# TRACKER_SOM_EVAL_BOARD_v1_0.net
KiCad netlist of a schematic drawn in EAGLE
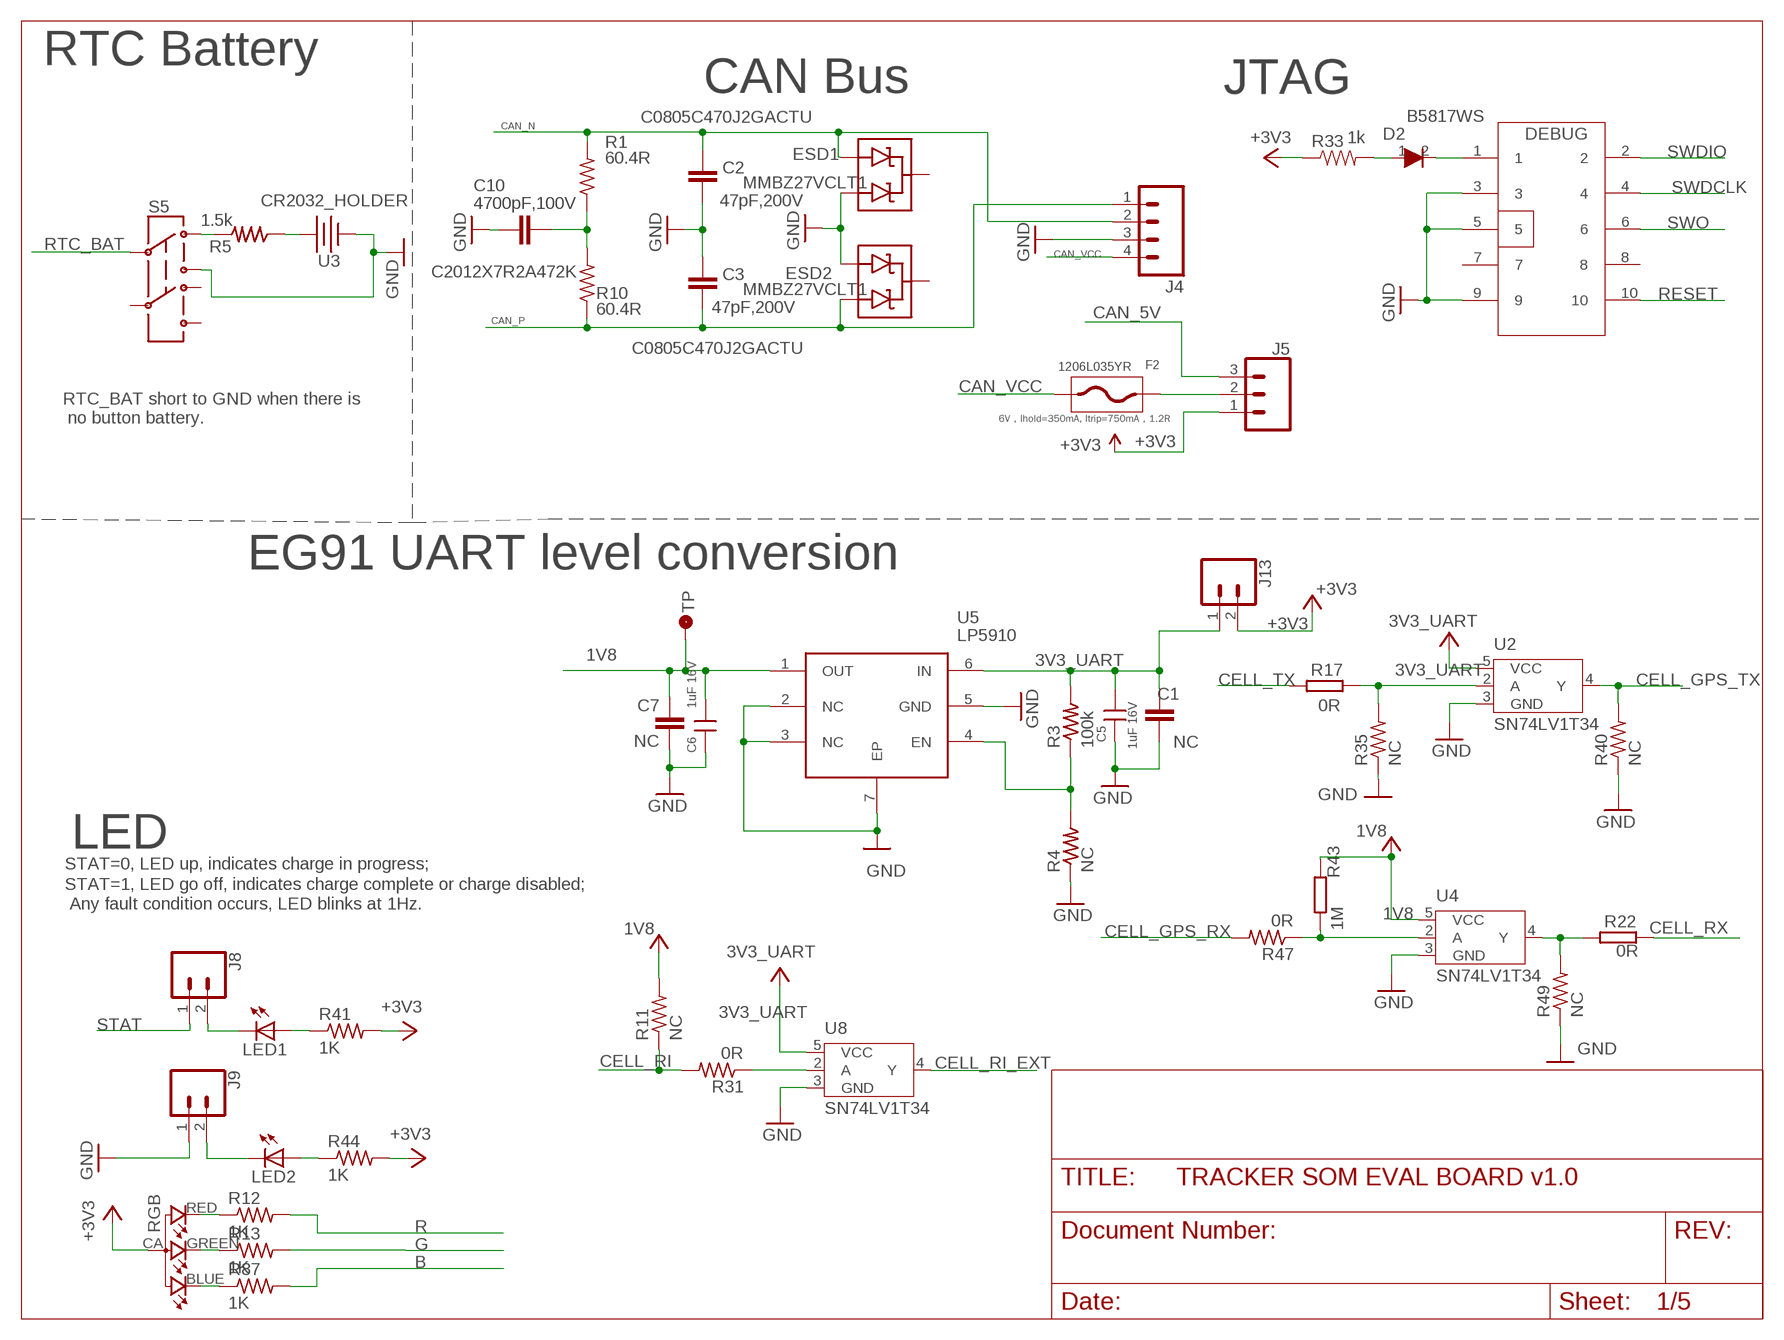
[diagram p0: schematic, sheet 1]
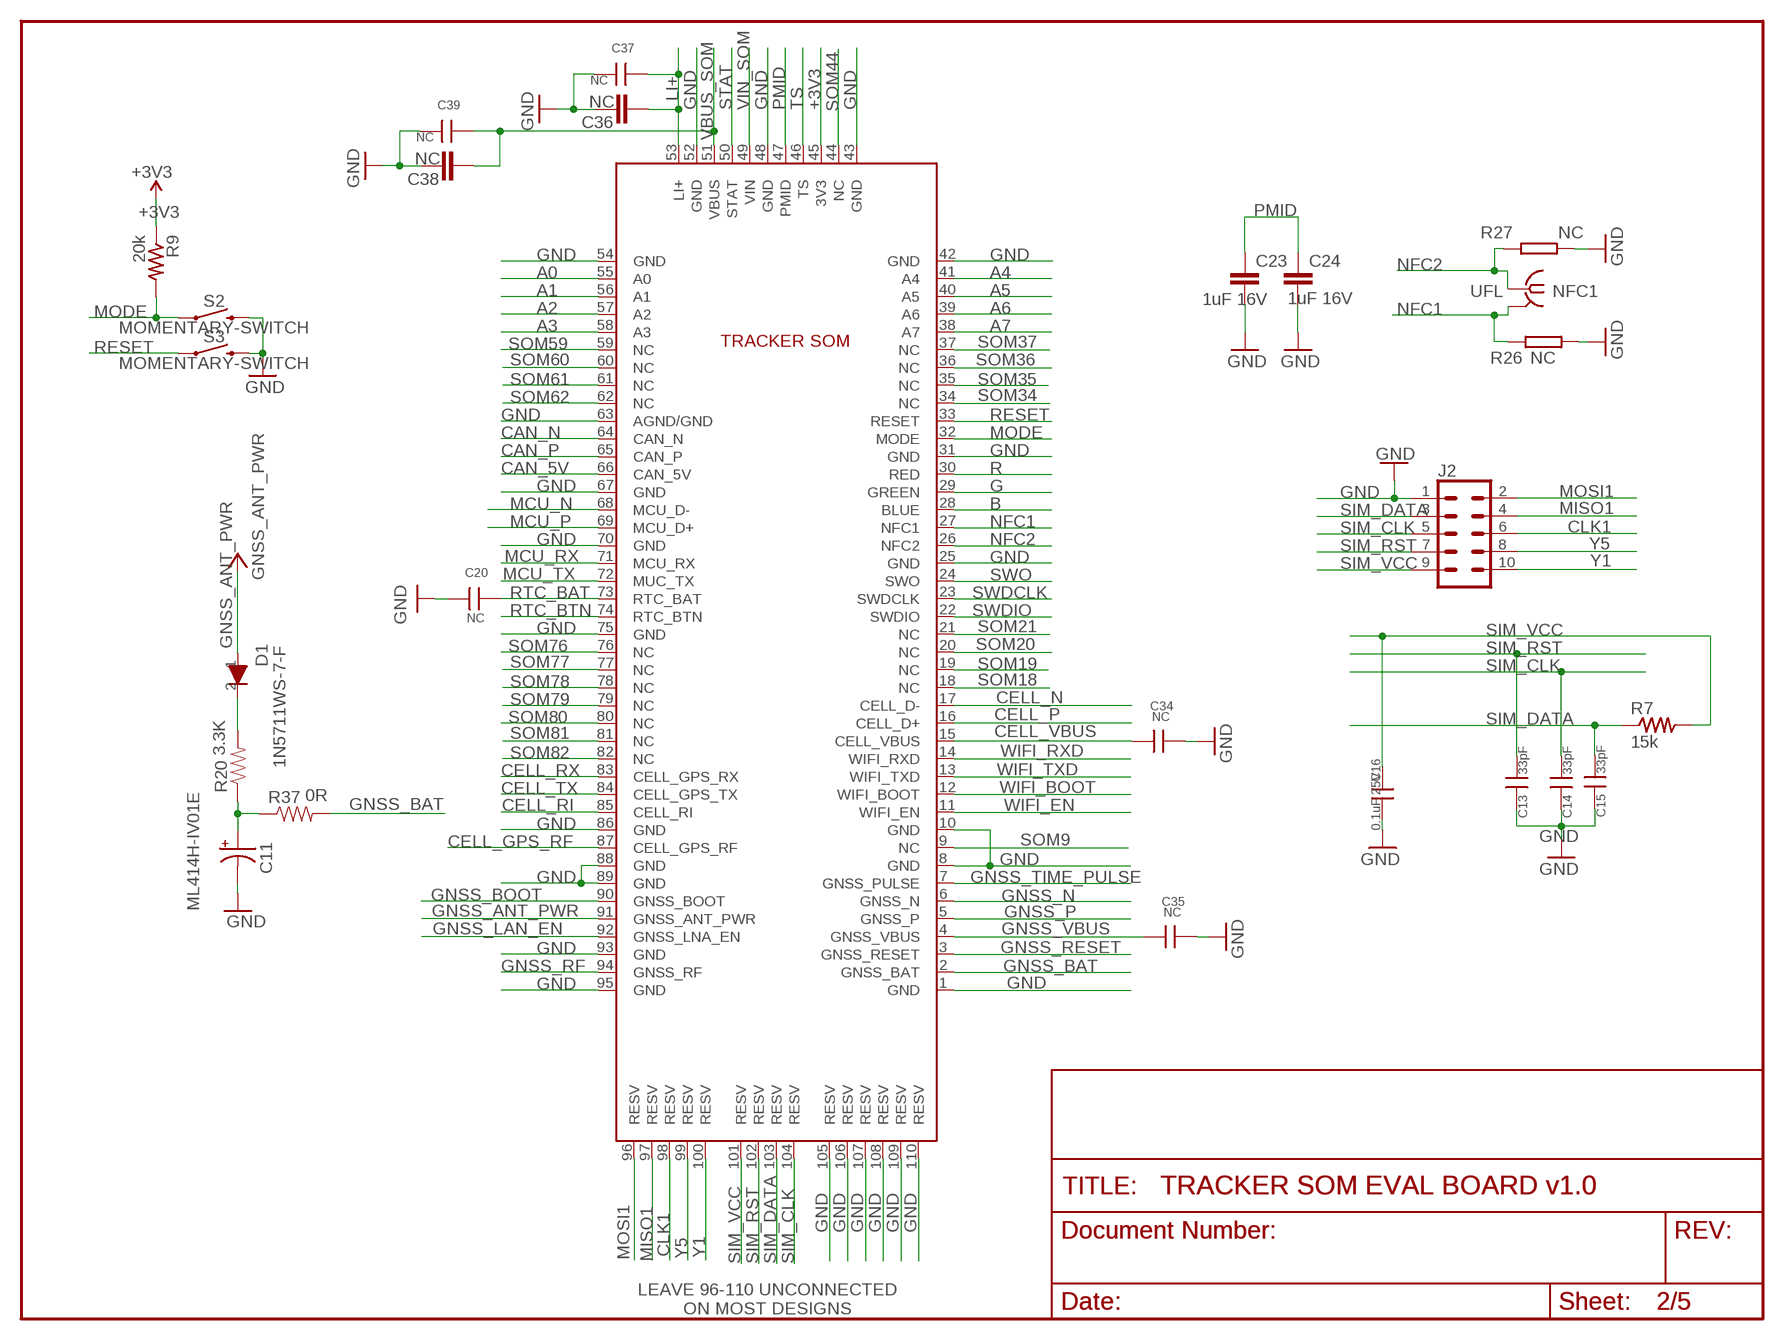
[diagram p1: schematic, sheet 2]
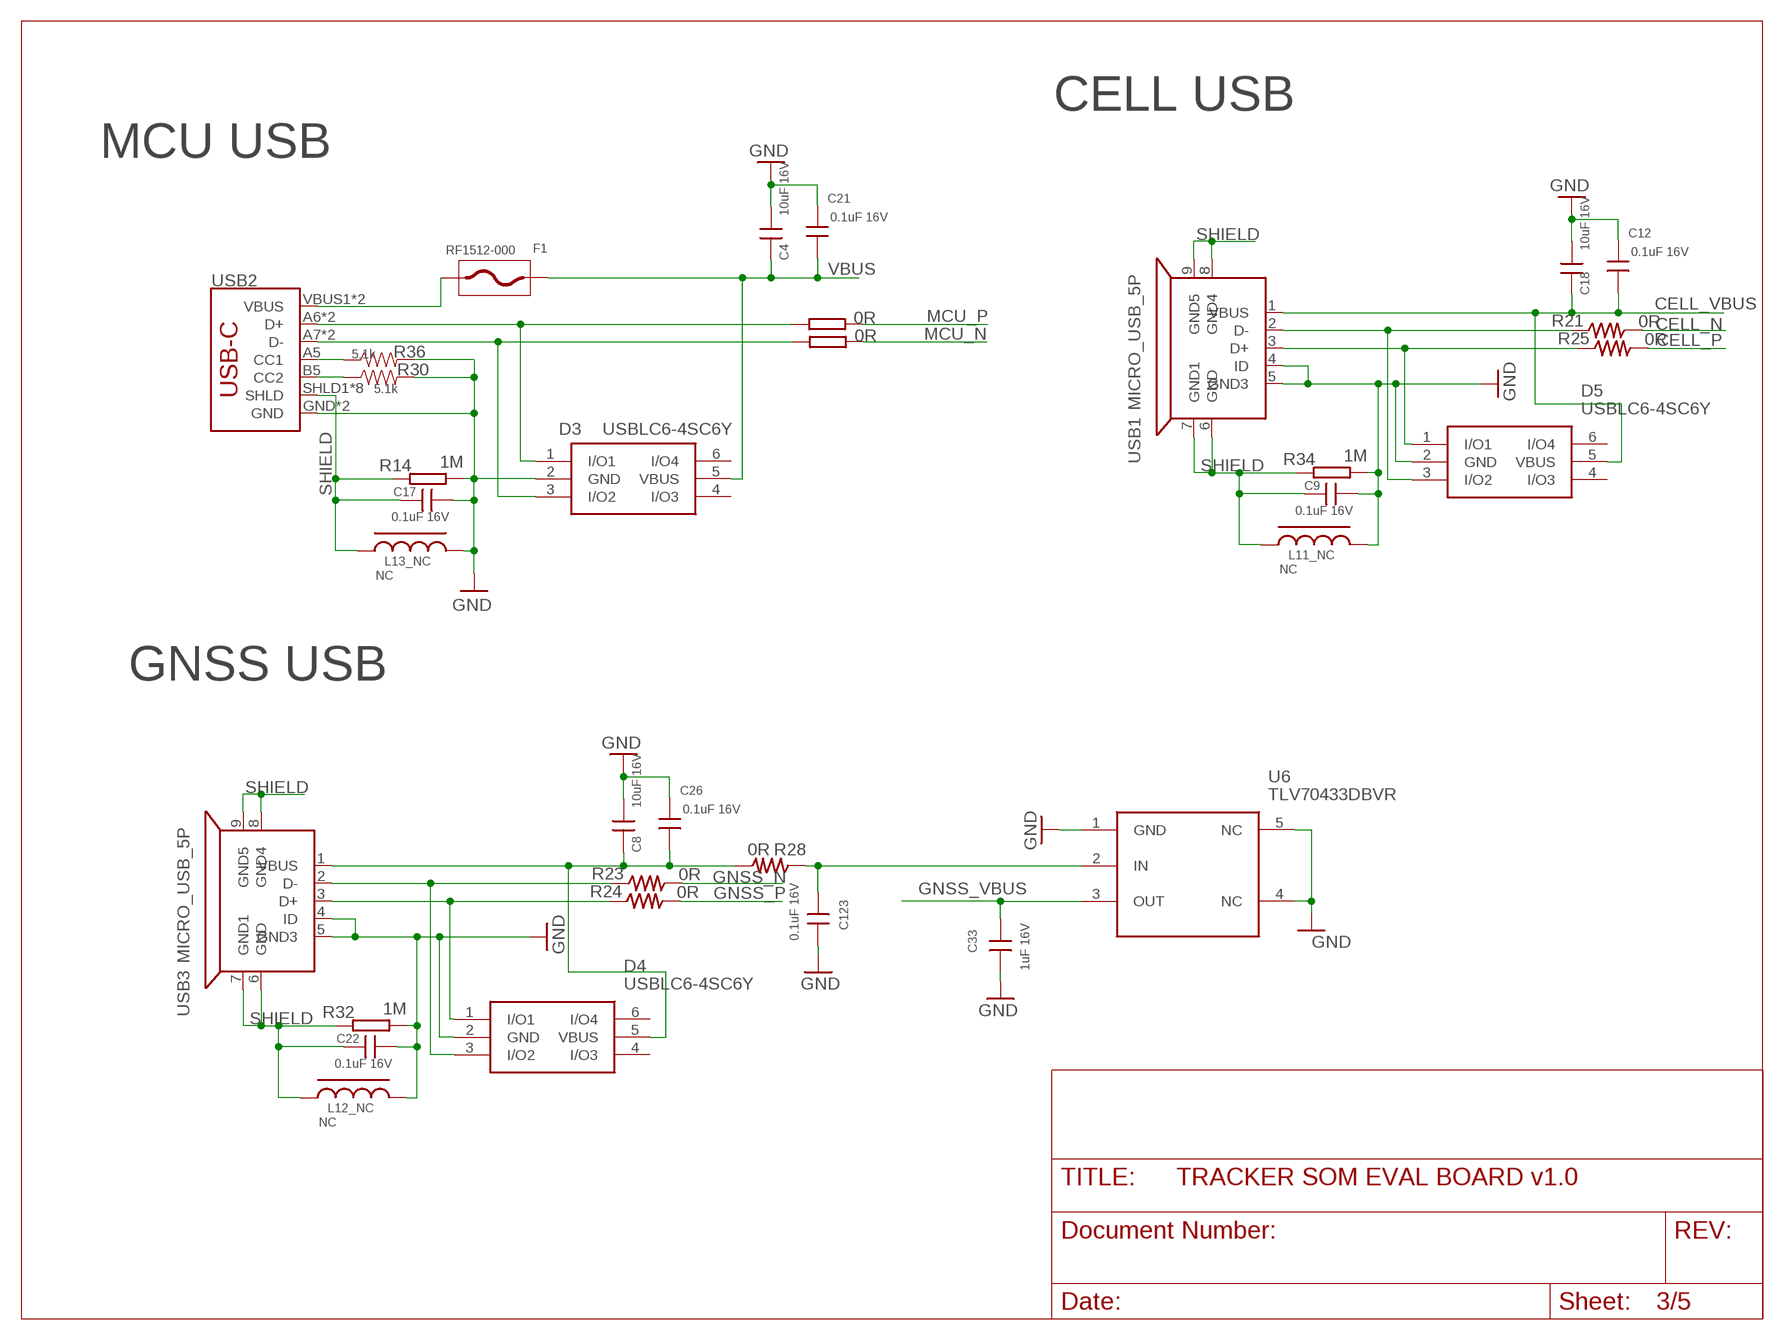
[diagram p2: schematic, sheet 3]
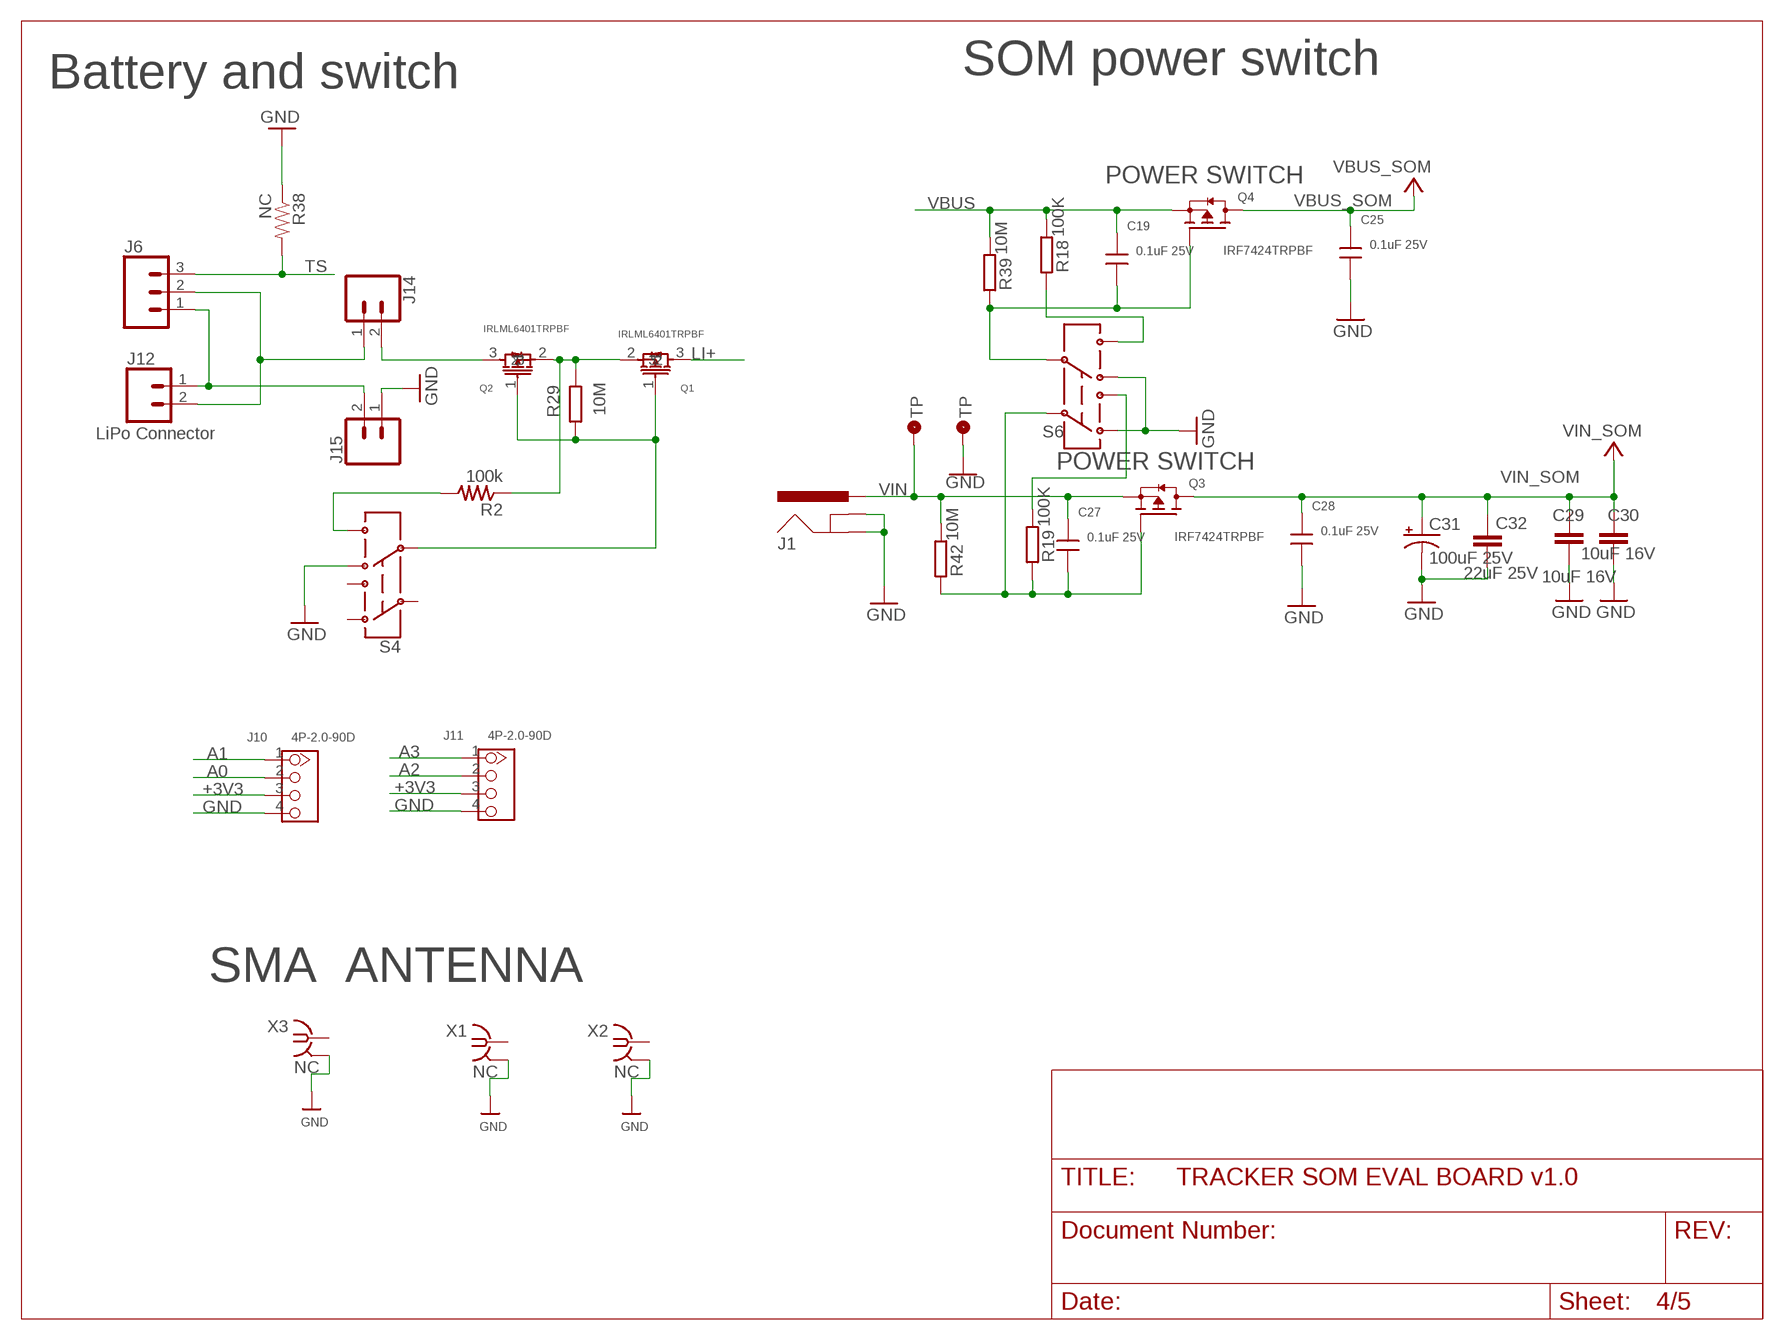
[diagram p3: schematic, sheet 4]
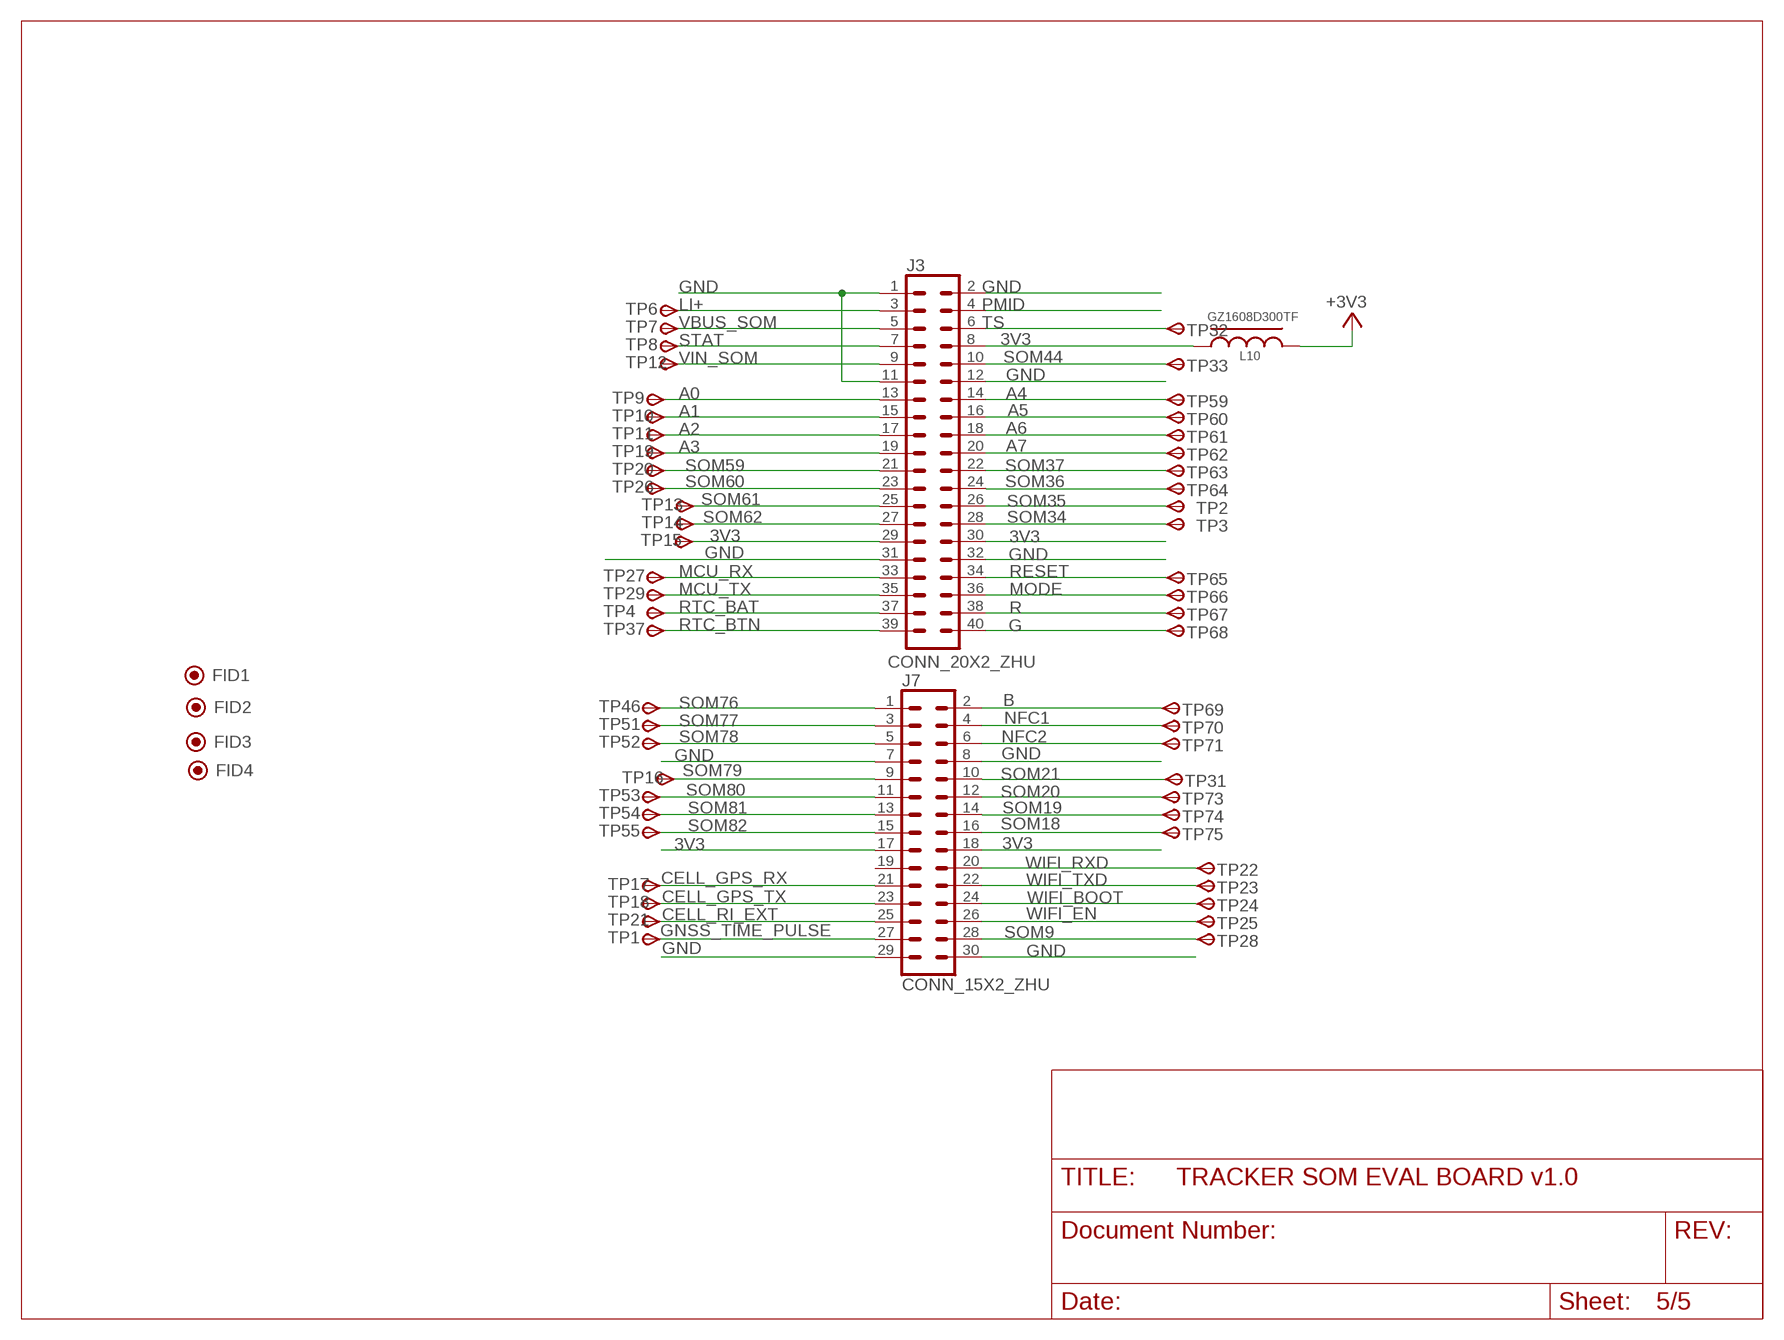
[diagram p4: schematic, sheet 5]

(export (version "E")
  (design (tool "Eeschema 10.0.6"))
  (components
    (comp (ref "FID1")
      (value "FIDUCIAL_2")
      (footprint "eagle-import:FID_TOP_1MM")
      (libsource (lib "eagle-import") (part "FIDUCIAL_2"))
    )
    (comp (ref "FID2")
      (value "FIDUCIAL_2")
      (footprint "eagle-import:FID_TOP_1MM")
      (libsource (lib "eagle-import") (part "FIDUCIAL_2"))
    )
    (comp (ref "FID3")
      (value "FIDUCIAL_2")
      (footprint "eagle-import:FID_TOP_1MM")
      (libsource (lib "eagle-import") (part "FIDUCIAL_2"))
    )
    (comp (ref "FID4")
      (value "FIDUCIAL_2")
      (footprint "eagle-import:FID_TOP_1MM")
      (libsource (lib "eagle-import") (part "FIDUCIAL_2"))
    )
    (comp (ref "J3")
      (value "CONN_20X2_ZHU")
      (footprint "eagle-import:SMD_2_20")
      (libsource (lib "eagle-import") (part "CONN_20X2_ZHU"))
    )
    (comp (ref "J7")
      (value "CONN_15X2_ZHU")
      (footprint "eagle-import:SMD_2_15")
      (libsource (lib "eagle-import") (part "CONN_15X2_ZHU"))
    )
    (comp (ref "L10")
      (value "GZ1608D300TF")
      (footprint "eagle-import:R-0603A")
      (libsource (lib "eagle-import") (part "L"))
    )
    (comp (ref "TP1")
      (value "TPSB1,27")
      (footprint "eagle-import:B1,27")
      (libsource (lib "eagle-import") (part "TPSB1,27"))
    )
    (comp (ref "TP2")
      (value "TPSB1,27")
      (footprint "eagle-import:B1,27")
      (libsource (lib "eagle-import") (part "TPSB1,27"))
    )
    (comp (ref "TP3")
      (value "TPSB1,27")
      (footprint "eagle-import:B1,27")
      (libsource (lib "eagle-import") (part "TPSB1,27"))
    )
    (comp (ref "TP4")
      (value "TPSB1,27")
      (footprint "eagle-import:B1,27")
      (libsource (lib "eagle-import") (part "TPSB1,27"))
    )
    (comp (ref "TP6")
      (value "TPSB1,27")
      (footprint "eagle-import:B1,27")
      (libsource (lib "eagle-import") (part "TPSB1,27"))
    )
    (comp (ref "TP7")
      (value "TPSB1,27")
      (footprint "eagle-import:B1,27")
      (libsource (lib "eagle-import") (part "TPSB1,27"))
    )
    (comp (ref "TP8")
      (value "TPSB1,27")
      (footprint "eagle-import:B1,27")
      (libsource (lib "eagle-import") (part "TPSB1,27"))
    )
    (comp (ref "TP9")
      (value "TPSB1,27")
      (footprint "eagle-import:B1,27")
      (libsource (lib "eagle-import") (part "TPSB1,27"))
    )
    (comp (ref "TP10")
      (value "TPSB1,27")
      (footprint "eagle-import:B1,27")
      (libsource (lib "eagle-import") (part "TPSB1,27"))
    )
    (comp (ref "TP11")
      (value "TPSB1,27")
      (footprint "eagle-import:B1,27")
      (libsource (lib "eagle-import") (part "TPSB1,27"))
    )
    (comp (ref "TP12")
      (value "TPSB1,27")
      (footprint "eagle-import:B1,27")
      (libsource (lib "eagle-import") (part "TPSB1,27"))
    )
    (comp (ref "TP13")
      (value "TPSB1,27")
      (footprint "eagle-import:B1,27")
      (libsource (lib "eagle-import") (part "TPSB1,27"))
    )
    (comp (ref "TP14")
      (value "TPSB1,27")
      (footprint "eagle-import:B1,27")
      (libsource (lib "eagle-import") (part "TPSB1,27"))
    )
    (comp (ref "TP15")
      (value "TPSB1,27")
      (footprint "eagle-import:B1,27")
      (libsource (lib "eagle-import") (part "TPSB1,27"))
    )
    (comp (ref "TP16")
      (value "TPSB1,27")
      (footprint "eagle-import:B1,27")
      (libsource (lib "eagle-import") (part "TPSB1,27"))
    )
    (comp (ref "TP17")
      (value "TPSB1,27")
      (footprint "eagle-import:B1,27")
      (libsource (lib "eagle-import") (part "TPSB1,27"))
    )
    (comp (ref "TP18")
      (value "TPSB1,27")
      (footprint "eagle-import:B1,27")
      (libsource (lib "eagle-import") (part "TPSB1,27"))
    )
    (comp (ref "TP19")
      (value "TPSB1,27")
      (footprint "eagle-import:B1,27")
      (libsource (lib "eagle-import") (part "TPSB1,27"))
    )
    (comp (ref "TP20")
      (value "TPSB1,27")
      (footprint "eagle-import:B1,27")
      (libsource (lib "eagle-import") (part "TPSB1,27"))
    )
    (comp (ref "TP21")
      (value "TPSB1,27")
      (footprint "eagle-import:B1,27")
      (libsource (lib "eagle-import") (part "TPSB1,27"))
    )
    (comp (ref "TP22")
      (value "TPSB1,27")
      (footprint "eagle-import:B1,27")
      (libsource (lib "eagle-import") (part "TPSB1,27"))
    )
    (comp (ref "TP23")
      (value "TPSB1,27")
      (footprint "eagle-import:B1,27")
      (libsource (lib "eagle-import") (part "TPSB1,27"))
    )
    (comp (ref "TP24")
      (value "TPSB1,27")
      (footprint "eagle-import:B1,27")
      (libsource (lib "eagle-import") (part "TPSB1,27"))
    )
    (comp (ref "TP25")
      (value "TPSB1,27")
      (footprint "eagle-import:B1,27")
      (libsource (lib "eagle-import") (part "TPSB1,27"))
    )
    (comp (ref "TP26")
      (value "TPSB1,27")
      (footprint "eagle-import:B1,27")
      (libsource (lib "eagle-import") (part "TPSB1,27"))
    )
    (comp (ref "TP27")
      (value "TPSB1,27")
      (footprint "eagle-import:B1,27")
      (libsource (lib "eagle-import") (part "TPSB1,27"))
    )
    (comp (ref "TP28")
      (value "TPSB1,27")
      (footprint "eagle-import:B1,27")
      (libsource (lib "eagle-import") (part "TPSB1,27"))
    )
    (comp (ref "TP29")
      (value "TPSB1,27")
      (footprint "eagle-import:B1,27")
      (libsource (lib "eagle-import") (part "TPSB1,27"))
    )
    (comp (ref "TP31")
      (value "TPSB1,27")
      (footprint "eagle-import:B1,27")
      (libsource (lib "eagle-import") (part "TPSB1,27"))
    )
    (comp (ref "TP32")
      (value "TPSB1,27")
      (footprint "eagle-import:B1,27")
      (libsource (lib "eagle-import") (part "TPSB1,27"))
    )
    (comp (ref "TP33")
      (value "TPSB1,27")
      (footprint "eagle-import:B1,27")
      (libsource (lib "eagle-import") (part "TPSB1,27"))
    )
    (comp (ref "TP37")
      (value "TPSB1,27")
      (footprint "eagle-import:B1,27")
      (libsource (lib "eagle-import") (part "TPSB1,27"))
    )
    (comp (ref "TP46")
      (value "TPSB1,27")
      (footprint "eagle-import:B1,27")
      (libsource (lib "eagle-import") (part "TPSB1,27"))
    )
    (comp (ref "TP51")
      (value "TPSB1,27")
      (footprint "eagle-import:B1,27")
      (libsource (lib "eagle-import") (part "TPSB1,27"))
    )
    (comp (ref "TP52")
      (value "TPSB1,27")
      (footprint "eagle-import:B1,27")
      (libsource (lib "eagle-import") (part "TPSB1,27"))
    )
    (comp (ref "TP53")
      (value "TPSB1,27")
      (footprint "eagle-import:B1,27")
      (libsource (lib "eagle-import") (part "TPSB1,27"))
    )
    (comp (ref "TP54")
      (value "TPSB1,27")
      (footprint "eagle-import:B1,27")
      (libsource (lib "eagle-import") (part "TPSB1,27"))
    )
    (comp (ref "TP55")
      (value "TPSB1,27")
      (footprint "eagle-import:B1,27")
      (libsource (lib "eagle-import") (part "TPSB1,27"))
    )
    (comp (ref "TP59")
      (value "TPSB1,27")
      (footprint "eagle-import:B1,27")
      (libsource (lib "eagle-import") (part "TPSB1,27"))
    )
    (comp (ref "TP60")
      (value "TPSB1,27")
      (footprint "eagle-import:B1,27")
      (libsource (lib "eagle-import") (part "TPSB1,27"))
    )
    (comp (ref "TP61")
      (value "TPSB1,27")
      (footprint "eagle-import:B1,27")
      (libsource (lib "eagle-import") (part "TPSB1,27"))
    )
    (comp (ref "TP62")
      (value "TPSB1,27")
      (footprint "eagle-import:B1,27")
      (libsource (lib "eagle-import") (part "TPSB1,27"))
    )
    (comp (ref "TP63")
      (value "TPSB1,27")
      (footprint "eagle-import:B1,27")
      (libsource (lib "eagle-import") (part "TPSB1,27"))
    )
    (comp (ref "TP64")
      (value "TPSB1,27")
      (footprint "eagle-import:B1,27")
      (libsource (lib "eagle-import") (part "TPSB1,27"))
    )
    (comp (ref "TP65")
      (value "TPSB1,27")
      (footprint "eagle-import:B1,27")
      (libsource (lib "eagle-import") (part "TPSB1,27"))
    )
    (comp (ref "TP66")
      (value "TPSB1,27")
      (footprint "eagle-import:B1,27")
      (libsource (lib "eagle-import") (part "TPSB1,27"))
    )
    (comp (ref "TP67")
      (value "TPSB1,27")
      (footprint "eagle-import:B1,27")
      (libsource (lib "eagle-import") (part "TPSB1,27"))
    )
    (comp (ref "TP68")
      (value "TPSB1,27")
      (footprint "eagle-import:B1,27")
      (libsource (lib "eagle-import") (part "TPSB1,27"))
    )
    (comp (ref "TP69")
      (value "TPSB1,27")
      (footprint "eagle-import:B1,27")
      (libsource (lib "eagle-import") (part "TPSB1,27"))
    )
    (comp (ref "TP70")
      (value "TPSB1,27")
      (footprint "eagle-import:B1,27")
      (libsource (lib "eagle-import") (part "TPSB1,27"))
    )
    (comp (ref "TP71")
      (value "TPSB1,27")
      (footprint "eagle-import:B1,27")
      (libsource (lib "eagle-import") (part "TPSB1,27"))
    )
    (comp (ref "TP73")
      (value "TPSB1,27")
      (footprint "eagle-import:B1,27")
      (libsource (lib "eagle-import") (part "TPSB1,27"))
    )
    (comp (ref "TP74")
      (value "TPSB1,27")
      (footprint "eagle-import:B1,27")
      (libsource (lib "eagle-import") (part "TPSB1,27"))
    )
    (comp (ref "TP75")
      (value "TPSB1,27")
      (footprint "eagle-import:B1,27")
      (libsource (lib "eagle-import") (part "TPSB1,27"))
    )
    (comp (ref "C4")
      (value "10uF 16V")
      (footprint "eagle-import:REDBEAR_C0603")
      (libsource (lib "eagle-import") (part "REDBEAR_CAPC0603"))
    )
    (comp (ref "C8")
      (value "10uF 16V")
      (footprint "eagle-import:REDBEAR_C0603")
      (libsource (lib "eagle-import") (part "REDBEAR_CAPC0603"))
    )
    (comp (ref "C9")
      (value "0.1uF 16V")
      (footprint "eagle-import:PARTICLE-SZ_C-0402")
      (libsource (lib "eagle-import") (part "PARTICLE-SZ_CAP0402"))
    )
    (comp (ref "C12")
      (value "0.1uF 16V")
      (footprint "eagle-import:C-0402")
      (libsource (lib "eagle-import") (part "RedBear_CAP0402"))
    )
    (comp (ref "C17")
      (value "0.1uF 16V")
      (footprint "eagle-import:PARTICLE-SZ_C-0402")
      (libsource (lib "eagle-import") (part "PARTICLE-SZ_CAP0402"))
    )
    (comp (ref "C18")
      (value "10uF 16V")
      (footprint "eagle-import:REDBEAR_C0603")
      (libsource (lib "eagle-import") (part "REDBEAR_CAPC0603"))
    )
    (comp (ref "C21")
      (value "0.1uF 16V")
      (footprint "eagle-import:C-0402")
      (libsource (lib "eagle-import") (part "RedBear_CAP0402"))
    )
    (comp (ref "C22")
      (value "0.1uF 16V")
      (footprint "eagle-import:PARTICLE-SZ_C-0402")
      (libsource (lib "eagle-import") (part "PARTICLE-SZ_CAP0402"))
    )
    (comp (ref "C26")
      (value "0.1uF 16V")
      (footprint "eagle-import:C-0402")
      (libsource (lib "eagle-import") (part "RedBear_CAP0402"))
    )
    (comp (ref "C33")
      (value "1uF 16V")
      (footprint "eagle-import:C0603")
      (libsource (lib "eagle-import") (part "CAPC0603"))
    )
    (comp (ref "C123")
      (value "0.1uF 16V")
      (footprint "eagle-import:C-0402")
      (libsource (lib "eagle-import") (part "particle SZ_CAP0402"))
    )
    (comp (ref "D3")
      (value "USBLC6-4SC6Y")
      (footprint "eagle-import:SOT95P280X145-6N")
      (fields (field (name "MOUSER_PART_NUMBER") "511-USBLC6-4SC6Y"))
      (libsource (lib "eagle-import") (part "USBLC6-4SC6Y"))
    )
    (comp (ref "D4")
      (value "USBLC6-4SC6Y")
      (footprint "eagle-import:SOT95P280X145-6N")
      (fields (field (name "MOUSER_PART_NUMBER") "511-USBLC6-4SC6Y"))
      (libsource (lib "eagle-import") (part "USBLC6-4SC6Y"))
    )
    (comp (ref "D5")
      (value "USBLC6-4SC6Y")
      (footprint "eagle-import:SOT95P280X145-6N")
      (fields (field (name "MOUSER_PART_NUMBER") "511-USBLC6-4SC6Y"))
      (libsource (lib "eagle-import") (part "USBLC6-4SC6Y"))
    )
    (comp (ref "F1")
      (value "RF1512-000")
      (footprint "eagle-import:R1206")
      (libsource (lib "eagle-import") (part "FUSEF1206"))
    )
    (comp (ref "L11_NC")
      (value "NC")
      (footprint "eagle-import:R-0603A")
      (libsource (lib "eagle-import") (part "L"))
    )
    (comp (ref "L12_NC")
      (value "NC")
      (footprint "eagle-import:R-0603A")
      (libsource (lib "eagle-import") (part "L"))
    )
    (comp (ref "L13_NC")
      (value "NC")
      (footprint "eagle-import:R-0603A")
      (libsource (lib "eagle-import") (part "L"))
    )
    (comp (ref "R14")
      (value "1M")
      (footprint "eagle-import:REDBEAR_R0603")
      (libsource (lib "eagle-import") (part "REDBEAR_RESR0603"))
    )
    (comp (ref "R15")
      (value "0R")
      (footprint "eagle-import:R-0402S")
      (libsource (lib "eagle-import") (part "RES0402S"))
    )
    (comp (ref "R16")
      (value "0R")
      (footprint "eagle-import:R-0402S")
      (libsource (lib "eagle-import") (part "RES0402S"))
    )
    (comp (ref "R21")
      (value "0R")
      (footprint "eagle-import:R-0402S")
      (libsource (lib "eagle-import") (part "particle SZ_RES0402S"))
    )
    (comp (ref "R23")
      (value "0R")
      (footprint "eagle-import:R-0402S")
      (libsource (lib "eagle-import") (part "particle SZ_RES0402S"))
    )
    (comp (ref "R24")
      (value "0R")
      (footprint "eagle-import:R-0402S")
      (libsource (lib "eagle-import") (part "particle SZ_RES0402S"))
    )
    (comp (ref "R25")
      (value "0R")
      (footprint "eagle-import:R-0402S")
      (libsource (lib "eagle-import") (part "particle SZ_RES0402S"))
    )
    (comp (ref "R28")
      (value "0R")
      (footprint "eagle-import:R-0402S")
      (libsource (lib "eagle-import") (part "particle SZ_RES0402S"))
    )
    (comp (ref "R30")
      (value "5.1k")
      (footprint "eagle-import:C0402")
      (libsource (lib "eagle-import") (part "SparkFun_RESISTOR0402"))
    )
    (comp (ref "R32")
      (value "1M")
      (footprint "eagle-import:REDBEAR_R0603")
      (libsource (lib "eagle-import") (part "REDBEAR_RESR0603"))
    )
    (comp (ref "R34")
      (value "1M")
      (footprint "eagle-import:REDBEAR_R0603")
      (libsource (lib "eagle-import") (part "REDBEAR_RESR0603"))
    )
    (comp (ref "R36")
      (value "5.1k")
      (footprint "eagle-import:C0402")
      (libsource (lib "eagle-import") (part "SparkFun_RESISTOR0402"))
    )
    (comp (ref "U6")
      (value "TLV70433DBVR")
      (footprint "eagle-import:TLV70433DBVR")
      (libsource (lib "eagle-import") (part "TLV70433DBVR"))
    )
    (comp (ref "USB1")
      (value "MICRO_USB_5P")
      (footprint "eagle-import:MICRO_USB")
      (libsource (lib "eagle-import") (part "MICRO_USBMICRO_USB"))
    )
    (comp (ref "USB2")
      (value "USB_C16PIN")
      (footprint "eagle-import:USB-C-16P")
      (libsource (lib "eagle-import") (part "USB_C16PIN"))
    )
    (comp (ref "USB3")
      (value "MICRO_USB_5P")
      (footprint "eagle-import:MICRO_USB")
      (libsource (lib "eagle-import") (part "MICRO_USBMICRO_USB"))
    )
    (comp (ref "C1")
      (value "NC")
      (footprint "eagle-import:C0805")
      (libsource (lib "eagle-import") (part "C-EUC0805"))
    )
    (comp (ref "C2")
      (value "47pF,200V")
      (footprint "eagle-import:C0805")
      (fields (field (name "PART_NUMBER") "C0805C470J2GACTU"))
      (libsource (lib "eagle-import") (part "C-EUC0805"))
    )
    (comp (ref "C3")
      (value "47pF,200V")
      (footprint "eagle-import:C0805")
      (fields (field (name "PART_NUMBER") "C0805C470J2GACTU"))
      (libsource (lib "eagle-import") (part "C-EUC0805"))
    )
    (comp (ref "C5")
      (value "1uF 16V")
      (footprint "eagle-import:C0603")
      (libsource (lib "eagle-import") (part "CAPC0603"))
    )
    (comp (ref "C6")
      (value "1uF 16V")
      (footprint "eagle-import:C0603")
      (libsource (lib "eagle-import") (part "CAPC0603"))
    )
    (comp (ref "C7")
      (value "NC")
      (footprint "eagle-import:C0805")
      (libsource (lib "eagle-import") (part "C-EUC0805"))
    )
    (comp (ref "C10")
      (value "4700pF,100V")
      (footprint "eagle-import:C0805")
      (fields (field (name "PART_NUMBER") "C2012X7R2A472K"))
      (libsource (lib "eagle-import") (part "C-EUC0805"))
    )
    (comp (ref "D2")
      (value "B5817WS")
      (footprint "eagle-import:SOD-323")
      (libsource (lib "eagle-import") (part "DIODESOD323"))
    )
    (comp (ref "DEBUG")
      (value "CON 2X5P")
      (footprint "eagle-import:CON5X2_1.27")
      (libsource (lib "eagle-import") (part "CON5X2"))
    )
    (comp (ref "ESD1")
      (value "MMBZ27VCLT1")
      (footprint "eagle-import:SOT23-3")
      (libsource (lib "eagle-import") (part "MMBZ27VCLT1"))
    )
    (comp (ref "ESD2")
      (value "MMBZ27VCLT1")
      (footprint "eagle-import:SOT23-3")
      (libsource (lib "eagle-import") (part "MMBZ27VCLT1"))
    )
    (comp (ref "F2")
      (value "1206L035YR")
      (footprint "eagle-import:R1206")
      (libsource (lib "eagle-import") (part "FUSEF1206"))
    )
    (comp (ref "J4")
      (value "M04SCREW")
      (footprint "eagle-import:SCREWTERMINAL-3.5MM-4")
      (fields (field (name "PARTNO") "OSTTE040104"))
      (libsource (lib "eagle-import") (part "M04SCREW"))
    )
    (comp (ref "J5")
      (value "CONN_03_2.54MM")
      (footprint "eagle-import:1X03")
      (libsource (lib "eagle-import") (part "CONN_03_2.54MM"))
    )
    (comp (ref "J8")
      (value "CONN_02")
      (footprint "eagle-import:1X02")
      (libsource (lib "eagle-import") (part "CONN_02"))
    )
    (comp (ref "J9")
      (value "CONN_02")
      (footprint "eagle-import:1X02")
      (libsource (lib "eagle-import") (part "CONN_02"))
    )
    (comp (ref "J13")
      (value "CONN_02")
      (footprint "eagle-import:1X02")
      (libsource (lib "eagle-import") (part "CONN_02"))
    )
    (comp (ref "LED1")
      (value "LED0603")
      (footprint "eagle-import:LED-0603")
      (libsource (lib "eagle-import") (part "LED0603"))
    )
    (comp (ref "LED2")
      (value "LED0603")
      (footprint "eagle-import:LED-0603")
      (libsource (lib "eagle-import") (part "LED0603"))
    )
    (comp (ref "R1")
      (value "60.4R")
      (footprint "eagle-import:R1206")
      (libsource (lib "eagle-import") (part "rcl_334_R-US_R1206"))
    )
    (comp (ref "R3")
      (value "100k")
      (footprint "eagle-import:R-0402S")
      (libsource (lib "eagle-import") (part "particle SZ_RES0402S"))
    )
    (comp (ref "R4")
      (value "NC")
      (footprint "eagle-import:R-0402S")
      (libsource (lib "eagle-import") (part "particle SZ_RES0402S"))
    )
    (comp (ref "R5")
      (value "1.5k")
      (footprint "eagle-import:R-0402S")
      (libsource (lib "eagle-import") (part "particle SZ_RES0402S"))
    )
    (comp (ref "R10")
      (value "60.4R")
      (footprint "eagle-import:R1206")
      (libsource (lib "eagle-import") (part "rcl_334_R-US_R1206"))
    )
    (comp (ref "R11")
      (value "NC")
      (footprint "eagle-import:R0402_B")
      (libsource (lib "eagle-import") (part "R-US_"))
    )
    (comp (ref "R12")
      (value "1K")
      (footprint "eagle-import:R0603")
      (libsource (lib "eagle-import") (part "R-US_R0603"))
    )
    (comp (ref "R13")
      (value "1K")
      (footprint "eagle-import:R0603")
      (libsource (lib "eagle-import") (part "R-US_R0603"))
    )
    (comp (ref "R17")
      (value "0R")
      (footprint "eagle-import:R0603")
      (libsource (lib "eagle-import") (part "RESR0603"))
    )
    (comp (ref "R22")
      (value "0R")
      (footprint "eagle-import:R0603")
      (libsource (lib "eagle-import") (part "RESR0603"))
    )
    (comp (ref "R31")
      (value "0R")
      (footprint "eagle-import:R0402_B")
      (libsource (lib "eagle-import") (part "R-US_"))
    )
    (comp (ref "R33")
      (value "1k")
      (footprint "eagle-import:0603")
      (libsource (lib "eagle-import") (part "RESISTOR0603"))
    )
    (comp (ref "R35")
      (value "NC")
      (footprint "eagle-import:R0402_B")
      (libsource (lib "eagle-import") (part "R-US_"))
    )
    (comp (ref "R40")
      (value "NC")
      (footprint "eagle-import:R0402_B")
      (libsource (lib "eagle-import") (part "R-US_"))
    )
    (comp (ref "R41")
      (value "1K")
      (footprint "eagle-import:R0603")
      (libsource (lib "eagle-import") (part "R-US_R0603"))
    )
    (comp (ref "R43")
      (value "1M")
      (footprint "eagle-import:REDBEAR_R0603")
      (libsource (lib "eagle-import") (part "REDBEAR_RESR0603"))
    )
    (comp (ref "R44")
      (value "1K")
      (footprint "eagle-import:R0603")
      (libsource (lib "eagle-import") (part "R-US_R0603"))
    )
    (comp (ref "R47")
      (value "0R")
      (footprint "eagle-import:R0402_B")
      (libsource (lib "eagle-import") (part "R-US_"))
    )
    (comp (ref "R49")
      (value "NC")
      (footprint "eagle-import:R0402_B")
      (libsource (lib "eagle-import") (part "R-US_"))
    )
    (comp (ref "R87")
      (value "1K")
      (footprint "eagle-import:R0603")
      (libsource (lib "eagle-import") (part "R-US_R0603"))
    )
    (comp (ref "RGB")
      (value "RGB-LED-CLMVB-FKARGB")
      (footprint "eagle-import:PLCC4-2MM-RGB")
      (libsource (lib "eagle-import") (part "RGB-LED-CLMVB-FKARGB"))
    )
    (comp (ref "S5")
      (value "SWITCH-DPDT")
      (footprint "eagle-import:SWITCH-2.5X3.2-6")
      (libsource (lib "eagle-import") (part "SWITCH-DPDT"))
    )
    (comp (ref "U$4")
      (value "TP5")
      (footprint "eagle-import:TP30_TOP")
      (libsource (lib "eagle-import") (part "TP5"))
    )
    (comp (ref "U2")
      (value "SN74LV1T34")
      (footprint "eagle-import:SC70-5")
      (libsource (lib "eagle-import") (part "SN74LV1T34"))
    )
    (comp (ref "U3")
      (value "CR2032_HOLDER")
      (footprint "eagle-import:CR2032_HOLDER")
      (libsource (lib "eagle-import") (part "CR2032_HOLDER"))
    )
    (comp (ref "U4")
      (value "SN74LV1T34")
      (footprint "eagle-import:SC70-5")
      (libsource (lib "eagle-import") (part "SN74LV1T34"))
    )
    (comp (ref "U5")
      (value "LP5910")
      (footprint "eagle-import:QFN6P")
      (libsource (lib "eagle-import") (part "LP5910"))
    )
    (comp (ref "U8")
      (value "SN74LV1T34")
      (footprint "eagle-import:SC70-5")
      (libsource (lib "eagle-import") (part "SN74LV1T34"))
    )
    (comp (ref "C11")
      (value "ML414H-IV01E")
      (footprint "eagle-import:ML414H")
      (libsource (lib "eagle-import") (part "ML414HIV01E"))
    )
    (comp (ref "C13")
      (value "33pF")
      (footprint "eagle-import:C-0402")
      (libsource (lib "eagle-import") (part "RedBear_CAP0402"))
    )
    (comp (ref "C14")
      (value "33pF")
      (footprint "eagle-import:C-0402")
      (libsource (lib "eagle-import") (part "RedBear_CAP0402"))
    )
    (comp (ref "C15")
      (value "33pF")
      (footprint "eagle-import:C-0402")
      (libsource (lib "eagle-import") (part "RedBear_CAP0402"))
    )
    (comp (ref "C16")
      (value "0.1uF 25V")
      (footprint "eagle-import:C-0402")
      (libsource (lib "eagle-import") (part "RedBear_CAP0402"))
    )
    (comp (ref "C20")
      (value "NC")
      (footprint "eagle-import:C-0402")
      (libsource (lib "eagle-import") (part "RedBear_CAP0402"))
    )
    (comp (ref "C23")
      (value "1uF 16V")
      (footprint "eagle-import:C0805")
      (libsource (lib "eagle-import") (part "C-EUC0805"))
    )
    (comp (ref "C24")
      (value "1uF 16V")
      (footprint "eagle-import:C0805")
      (libsource (lib "eagle-import") (part "C-EUC0805"))
    )
    (comp (ref "C34")
      (value "NC")
      (footprint "eagle-import:C-0402")
      (libsource (lib "eagle-import") (part "RedBear_CAP0402"))
    )
    (comp (ref "C35")
      (value "NC")
      (footprint "eagle-import:C-0402")
      (libsource (lib "eagle-import") (part "RedBear_CAP0402"))
    )
    (comp (ref "C36")
      (value "NC")
      (footprint "eagle-import:C1206")
      (libsource (lib "eagle-import") (part "C-EUC1206"))
    )
    (comp (ref "C37")
      (value "NC")
      (footprint "eagle-import:C-0402")
      (libsource (lib "eagle-import") (part "RedBear_CAP0402"))
    )
    (comp (ref "C38")
      (value "NC")
      (footprint "eagle-import:C1206")
      (libsource (lib "eagle-import") (part "C-EUC1206"))
    )
    (comp (ref "C39")
      (value "NC")
      (footprint "eagle-import:C-0402")
      (libsource (lib "eagle-import") (part "RedBear_CAP0402"))
    )
    (comp (ref "D1")
      (value "1N5711WS-7-F")
      (footprint "eagle-import:SOD-323")
      (libsource (lib "eagle-import") (part "DIODESOD323"))
    )
    (comp (ref "J2")
      (value "CONN_05X2PTH")
      (footprint "eagle-import:2X5")
      (libsource (lib "eagle-import") (part "CONN_05X2PTH"))
    )
    (comp (ref "NFC1")
      (value "UFL")
      (footprint "eagle-import:IPEX-20279-001E")
      (libsource (lib "eagle-import") (part "IPEX-20279-001E"))
    )
    (comp (ref "R7")
      (value "15k")
      (footprint "eagle-import:R-0402S")
      (libsource (lib "eagle-import") (part "particle SZ_RES0402S"))
    )
    (comp (ref "R9")
      (value "20k")
      (footprint "eagle-import:R-0402S")
      (libsource (lib "eagle-import") (part "particle SZ_RES0402S"))
    )
    (comp (ref "R20")
      (value "3.3K")
      (footprint "eagle-import:0603")
      (libsource (lib "eagle-import") (part "RESISTOR0603"))
    )
    (comp (ref "R26")
      (value "NC")
      (footprint "eagle-import:R-0402S")
      (libsource (lib "eagle-import") (part "RES0402S"))
    )
    (comp (ref "R27")
      (value "NC")
      (footprint "eagle-import:R-0402S")
      (libsource (lib "eagle-import") (part "RES0402S"))
    )
    (comp (ref "R37")
      (value "0R")
      (footprint "eagle-import:0603")
      (libsource (lib "eagle-import") (part "RESISTOR0603"))
    )
    (comp (ref "S2")
      (value "MOMENTARY-SWITCH")
      (footprint "eagle-import:TACTILE_SWITCH_PTH_6.0MM")
      (libsource (lib "eagle-import") (part "MOMENTARY-SWITCH-SPST-PTH-6.0MM"))
    )
    (comp (ref "S3")
      (value "MOMENTARY-SWITCH")
      (footprint "eagle-import:TACTILE_SWITCH_PTH_6.0MM")
      (libsource (lib "eagle-import") (part "MOMENTARY-SWITCH-SPST-PTH-6.0MM"))
    )
    (comp (ref "U1")
      (value "TRACKER-SOM-3A")
      (footprint "eagle-import:TRACKER-SOM-3A")
      (libsource (lib "eagle-import") (part "TRACKER-SOM-3A"))
    )
    (comp (ref "C19")
      (value "0.1uF 25V")
      (footprint "eagle-import:C-0402")
      (libsource (lib "eagle-import") (part "RedBear_CAP0402"))
    )
    (comp (ref "C25")
      (value "0.1uF 25V")
      (footprint "eagle-import:C-0402")
      (libsource (lib "eagle-import") (part "RedBear_CAP0402"))
    )
    (comp (ref "C27")
      (value "0.1uF 25V")
      (footprint "eagle-import:C-0402")
      (libsource (lib "eagle-import") (part "RedBear_CAP0402"))
    )
    (comp (ref "C28")
      (value "0.1uF 25V")
      (footprint "eagle-import:C-0402")
      (libsource (lib "eagle-import") (part "RedBear_CAP0402"))
    )
    (comp (ref "C29")
      (value "10uF 16V")
      (footprint "eagle-import:C0805")
      (libsource (lib "eagle-import") (part "C-EUC0805"))
    )
    (comp (ref "C30")
      (value "10uF 16V")
      (footprint "eagle-import:C0805")
      (libsource (lib "eagle-import") (part "C-EUC0805"))
    )
    (comp (ref "C31")
      (value "100uF 25V")
      (footprint "eagle-import:PANASONIC_D")
      (libsource (lib "eagle-import") (part "100UF-POLAR-25V-20%(ELEC)"))
    )
    (comp (ref "C32")
      (value "22uF 25V")
      (footprint "eagle-import:C1206")
      (libsource (lib "eagle-import") (part "C-EUC1206"))
    )
    (comp (ref "J1")
      (value "POWER_JACKSLT")
      (footprint "eagle-import:POWER_JACK_SLOT")
      (libsource (lib "eagle-import") (part "POWER_JACKSLT"))
    )
    (comp (ref "J6")
      (value "CONN_03_2.54MM")
      (footprint "eagle-import:1X03")
      (libsource (lib "eagle-import") (part "CONN_03_2.54MM"))
    )
    (comp (ref "J10")
      (value "4P-2.0-90D")
      (footprint "eagle-import:HW4-2.0-90D")
      (libsource (lib "eagle-import") (part "GROVE-CONNECTOR-DIP-90D(4P-2.0)"))
    )
    (comp (ref "J11")
      (value "4P-2.0-90D")
      (footprint "eagle-import:HW4-2.0-90D")
      (libsource (lib "eagle-import") (part "GROVE-CONNECTOR-DIP-90D(4P-2.0)"))
    )
    (comp (ref "J12")
      (value "CONN_02-JST-2MM-SMT")
      (footprint "eagle-import:JST-2-SMD")
      (libsource (lib "eagle-import") (part "SparkFun-Connectors_CONN_02-JST-2MM-SMT"))
    )
    (comp (ref "J14")
      (value "CONN_02")
      (footprint "eagle-import:1X02")
      (libsource (lib "eagle-import") (part "CONN_02"))
    )
    (comp (ref "J15")
      (value "CONN_02")
      (footprint "eagle-import:1X02")
      (libsource (lib "eagle-import") (part "CONN_02"))
    )
    (comp (ref "Q1")
      (value "IRLML6401TRPBF")
      (footprint "eagle-import:SOT-23")
      (libsource (lib "eagle-import") (part "PMOS"))
    )
    (comp (ref "Q2")
      (value "IRLML6401TRPBF")
      (footprint "eagle-import:SOT-23")
      (libsource (lib "eagle-import") (part "PMOS"))
    )
    (comp (ref "Q3")
      (value "IRF7424TRPBF")
      (footprint "eagle-import:PMOS_IRF7424")
      (libsource (lib "eagle-import") (part "PMOS_IRF7424"))
    )
    (comp (ref "Q4")
      (value "IRF7424TRPBF")
      (footprint "eagle-import:PMOS_IRF7424")
      (libsource (lib "eagle-import") (part "PMOS_IRF7424"))
    )
    (comp (ref "R2")
      (value "100k")
      (footprint "eagle-import:R-0402S")
      (libsource (lib "eagle-import") (part "particle SZ_RES0402S"))
    )
    (comp (ref "R18")
      (value "100K")
      (footprint "eagle-import:R0603")
      (libsource (lib "eagle-import") (part "RESR0603"))
    )
    (comp (ref "R19")
      (value "100K")
      (footprint "eagle-import:R0603")
      (libsource (lib "eagle-import") (part "RESR0603"))
    )
    (comp (ref "R29")
      (value "10M")
      (footprint "eagle-import:R0603")
      (libsource (lib "eagle-import") (part "RESR0603"))
    )
    (comp (ref "R38")
      (value "NC")
      (footprint "eagle-import:0603-RES")
      (libsource (lib "eagle-import") (part "100OHM-1/10W-1%(0603)"))
    )
    (comp (ref "R39")
      (value "10M")
      (footprint "eagle-import:R0603")
      (libsource (lib "eagle-import") (part "RESR0603"))
    )
    (comp (ref "R42")
      (value "10M")
      (footprint "eagle-import:R0603")
      (libsource (lib "eagle-import") (part "RESR0603"))
    )
    (comp (ref "S4")
      (value "SWITCH-DPDT")
      (footprint "eagle-import:SWITCH-2.5X3.2-6")
      (libsource (lib "eagle-import") (part "SWITCH-DPDT"))
    )
    (comp (ref "S6")
      (value "SWITCH-DPDT")
      (footprint "eagle-import:SWITCH-2.5X3.2-6")
      (libsource (lib "eagle-import") (part "SWITCH-DPDT"))
    )
    (comp (ref "U$9")
      (value "TP2")
      (footprint "eagle-import:TP70_BOT")
      (libsource (lib "eagle-import") (part "Spark_TP2"))
    )
    (comp (ref "U$10")
      (value "TP2")
      (footprint "eagle-import:TP70_BOT")
      (libsource (lib "eagle-import") (part "Spark_TP2"))
    )
    (comp (ref "X1")
      (value "NC")
      (footprint "eagle-import:BU-SMA-G")
      (libsource (lib "eagle-import") (part "BU-SMA-G"))
    )
    (comp (ref "X2")
      (value "NC")
      (footprint "eagle-import:BU-SMA-G")
      (libsource (lib "eagle-import") (part "BU-SMA-G"))
    )
    (comp (ref "X3")
      (value "NC")
      (footprint "eagle-import:BU-SMA-G")
      (libsource (lib "eagle-import") (part "BU-SMA-G"))
    )
  )
  (nets
    (net (code "1") (name "+3V3") (class "Default")
      (node (ref "J10") (pin "3") (pinfunction "3_3") (pintype "bidirectional"))
      (node (ref "J11") (pin "3") (pinfunction "3_3") (pintype "bidirectional"))
      (node (ref "J13") (pin "2") (pinfunction "2_2") (pintype "passive"))
      (node (ref "J5") (pin "1") (pinfunction "1_1") (pintype "passive"))
      (node (ref "L10") (pin "2") (pinfunction "2_2") (pintype "bidirectional"))
      (node (ref "R33") (pin "1") (pinfunction "1_1") (pintype "passive"))
      (node (ref "R41") (pin "2") (pinfunction "2_2") (pintype "passive"))
      (node (ref "R44") (pin "2") (pinfunction "2_2") (pintype "passive"))
      (node (ref "R9") (pin "1") (pinfunction "1_1") (pintype "bidirectional"))
      (node (ref "RGB") (pin "CA") (pinfunction "1_CA") (pintype "passive"))
      (node (ref "U1") (pin "45") (pinfunction "3V3_45") (pintype "bidirectional"))
    )
    (net (code "2") (name "1V8") (class "Default")
      (node (ref "C6") (pin "1") (pinfunction "1_1") (pintype "bidirectional"))
      (node (ref "C7") (pin "1") (pinfunction "1_1") (pintype "passive"))
      (node (ref "R11") (pin "2") (pinfunction "2_2") (pintype "passive"))
      (node (ref "R43") (pin "1") (pinfunction "1_1") (pintype "bidirectional"))
      (node (ref "U$4") (pin "P$1") (pinfunction "TP_P$1") (pintype "bidirectional"))
      (node (ref "U4") (pin "5") (pinfunction "VCC_5") (pintype "power_in"))
      (node (ref "U5") (pin "1") (pinfunction "OUT_1") (pintype "bidirectional"))
    )
    (net (code "3") (name "3V3") (class "Default")
      (node (ref "J3") (pin "29") (pinfunction "29_29") (pintype "passive"))
      (node (ref "J3") (pin "30") (pinfunction "30_30") (pintype "passive"))
      (node (ref "J3") (pin "8") (pinfunction "8_8") (pintype "passive"))
      (node (ref "J7") (pin "17") (pinfunction "17_17") (pintype "passive"))
      (node (ref "J7") (pin "18") (pinfunction "18_18") (pintype "passive"))
      (node (ref "L10") (pin "1") (pinfunction "1_1") (pintype "bidirectional"))
      (node (ref "TP15") (pin "TP") (pinfunction "PP_TP") (pintype "input"))
    )
    (net (code "4") (name "3V3_UART") (class "Default")
      (node (ref "C1") (pin "1") (pinfunction "1_1") (pintype "passive"))
      (node (ref "C5") (pin "1") (pinfunction "1_1") (pintype "bidirectional"))
      (node (ref "J13") (pin "1") (pinfunction "1_1") (pintype "passive"))
      (node (ref "R3") (pin "2") (pinfunction "2_2") (pintype "bidirectional"))
      (node (ref "U2") (pin "5") (pinfunction "VCC_5") (pintype "power_in"))
      (node (ref "U5") (pin "6") (pinfunction "IN_6") (pintype "bidirectional"))
      (node (ref "U8") (pin "5") (pinfunction "VCC_5") (pintype "power_in"))
    )
    (net (code "5") (name "A0") (class "Default")
      (node (ref "J10") (pin "2") (pinfunction "2_2") (pintype "bidirectional"))
      (node (ref "J3") (pin "13") (pinfunction "13_13") (pintype "passive"))
      (node (ref "TP9") (pin "TP") (pinfunction "PP_TP") (pintype "input"))
      (node (ref "U1") (pin "55") (pinfunction "A0_55") (pintype "bidirectional"))
    )
    (net (code "6") (name "A1") (class "Default")
      (node (ref "J10") (pin "1") (pinfunction "1_1") (pintype "bidirectional"))
      (node (ref "J3") (pin "15") (pinfunction "15_15") (pintype "passive"))
      (node (ref "TP10") (pin "TP") (pinfunction "PP_TP") (pintype "input"))
      (node (ref "U1") (pin "56") (pinfunction "A1_56") (pintype "bidirectional"))
    )
    (net (code "7") (name "A2") (class "Default")
      (node (ref "J11") (pin "2") (pinfunction "2_2") (pintype "bidirectional"))
      (node (ref "J3") (pin "17") (pinfunction "17_17") (pintype "passive"))
      (node (ref "TP11") (pin "TP") (pinfunction "PP_TP") (pintype "input"))
      (node (ref "U1") (pin "57") (pinfunction "A2_57") (pintype "bidirectional"))
    )
    (net (code "8") (name "A3") (class "Default")
      (node (ref "J11") (pin "1") (pinfunction "1_1") (pintype "bidirectional"))
      (node (ref "J3") (pin "19") (pinfunction "19_19") (pintype "passive"))
      (node (ref "TP19") (pin "TP") (pinfunction "PP_TP") (pintype "input"))
      (node (ref "U1") (pin "58") (pinfunction "A3_58") (pintype "bidirectional"))
    )
    (net (code "9") (name "A4") (class "Default")
      (node (ref "J3") (pin "14") (pinfunction "14_14") (pintype "passive"))
      (node (ref "TP59") (pin "TP") (pinfunction "PP_TP") (pintype "input"))
      (node (ref "U1") (pin "41") (pinfunction "A4_41") (pintype "bidirectional"))
    )
    (net (code "10") (name "A5") (class "Default")
      (node (ref "J3") (pin "16") (pinfunction "16_16") (pintype "passive"))
      (node (ref "TP60") (pin "TP") (pinfunction "PP_TP") (pintype "input"))
      (node (ref "U1") (pin "40") (pinfunction "A5_40") (pintype "bidirectional"))
    )
    (net (code "11") (name "A6") (class "Default")
      (node (ref "J3") (pin "18") (pinfunction "18_18") (pintype "passive"))
      (node (ref "TP61") (pin "TP") (pinfunction "PP_TP") (pintype "input"))
      (node (ref "U1") (pin "39") (pinfunction "A6_39") (pintype "bidirectional"))
    )
    (net (code "12") (name "A7") (class "Default")
      (node (ref "J3") (pin "20") (pinfunction "20_20") (pintype "passive"))
      (node (ref "TP62") (pin "TP") (pinfunction "PP_TP") (pintype "input"))
      (node (ref "U1") (pin "38") (pinfunction "A7_38") (pintype "bidirectional"))
    )
    (net (code "13") (name "B") (class "Default")
      (node (ref "J7") (pin "2") (pinfunction "2_2") (pintype "passive"))
      (node (ref "R87") (pin "2") (pinfunction "2_2") (pintype "passive"))
      (node (ref "TP69") (pin "TP") (pinfunction "PP_TP") (pintype "input"))
      (node (ref "U1") (pin "28") (pinfunction "BLUE_28") (pintype "bidirectional"))
    )
    (net (code "14") (name "CAN_5V") (class "Default")
      (node (ref "J5") (pin "3") (pinfunction "3_3") (pintype "passive"))
      (node (ref "U1") (pin "66") (pinfunction "CAN_5V_66") (pintype "bidirectional"))
    )
    (net (code "15") (name "CAN_N") (class "Default")
      (node (ref "C2") (pin "1") (pinfunction "1_1") (pintype "passive"))
      (node (ref "ESD1") (pin "2") (pinfunction "A2_2") (pintype "passive"))
      (node (ref "J4") (pin "2") (pinfunction "2_2") (pintype "passive"))
      (node (ref "R1") (pin "2") (pinfunction "2_2") (pintype "passive"))
      (node (ref "U1") (pin "64") (pinfunction "CAN_N_64") (pintype "bidirectional"))
    )
    (net (code "16") (name "CAN_P") (class "Default")
      (node (ref "C3") (pin "2") (pinfunction "2_2") (pintype "passive"))
      (node (ref "ESD2") (pin "1") (pinfunction "A1_1") (pintype "passive"))
      (node (ref "J4") (pin "1") (pinfunction "1_1") (pintype "passive"))
      (node (ref "R10") (pin "1") (pinfunction "1_1") (pintype "passive"))
      (node (ref "U1") (pin "65") (pinfunction "CAN_P_65") (pintype "bidirectional"))
    )
    (net (code "17") (name "CAN_VCC") (class "Default")
      (node (ref "F2") (pin "1") (pinfunction "1_1") (pintype "bidirectional"))
      (node (ref "J4") (pin "4") (pinfunction "4_4") (pintype "passive"))
    )
    (net (code "18") (name "CELL_GPS_RF") (class "Default")
      (node (ref "U1") (pin "87") (pinfunction "CELL_GPS_RF_87") (pintype "bidirectional"))
    )
    (net (code "19") (name "CELL_GPS_RX") (class "Default")
      (node (ref "J7") (pin "21") (pinfunction "21_21") (pintype "passive"))
      (node (ref "R47") (pin "2") (pinfunction "2_2") (pintype "passive"))
      (node (ref "TP17") (pin "TP") (pinfunction "PP_TP") (pintype "input"))
    )
    (net (code "20") (name "CELL_GPS_TX") (class "Default")
      (node (ref "J7") (pin "23") (pinfunction "23_23") (pintype "passive"))
      (node (ref "R40") (pin "2") (pinfunction "2_2") (pintype "passive"))
      (node (ref "TP18") (pin "TP") (pinfunction "PP_TP") (pintype "input"))
      (node (ref "U2") (pin "4") (pinfunction "Y_4") (pintype "bidirectional"))
    )
    (net (code "21") (name "CELL_N") (class "Default")
      (node (ref "R21") (pin "2") (pinfunction "2_2") (pintype "bidirectional"))
      (node (ref "U1") (pin "17") (pinfunction "CELL_D-_17") (pintype "bidirectional"))
    )
    (net (code "22") (name "CELL_P") (class "Default")
      (node (ref "R25") (pin "2") (pinfunction "2_2") (pintype "bidirectional"))
      (node (ref "U1") (pin "16") (pinfunction "CELL_D+_16") (pintype "bidirectional"))
    )
    (net (code "23") (name "CELL_RI") (class "Default")
      (node (ref "R11") (pin "1") (pinfunction "1_1") (pintype "passive"))
      (node (ref "R31") (pin "2") (pinfunction "2_2") (pintype "passive"))
      (node (ref "U1") (pin "85") (pinfunction "CELL_RI_85") (pintype "bidirectional"))
    )
    (net (code "24") (name "CELL_RI_EXT") (class "Default")
      (node (ref "J7") (pin "25") (pinfunction "25_25") (pintype "passive"))
      (node (ref "TP21") (pin "TP") (pinfunction "PP_TP") (pintype "input"))
      (node (ref "U8") (pin "4") (pinfunction "Y_4") (pintype "bidirectional"))
    )
    (net (code "25") (name "CELL_RX") (class "Default")
      (node (ref "R22") (pin "1") (pinfunction "1_1") (pintype "bidirectional"))
      (node (ref "U1") (pin "83") (pinfunction "CELL_GPS_RX_83") (pintype "bidirectional"))
    )
    (net (code "26") (name "CELL_TX") (class "Default")
      (node (ref "R17") (pin "2") (pinfunction "2_2") (pintype "bidirectional"))
      (node (ref "U1") (pin "84") (pinfunction "CELL_GPS_TX_84") (pintype "bidirectional"))
    )
    (net (code "27") (name "CELL_VBUS") (class "Default")
      (node (ref "C12") (pin "1") (pinfunction "1_1") (pintype "bidirectional"))
      (node (ref "C18") (pin "2") (pinfunction "2_2") (pintype "bidirectional"))
      (node (ref "C34") (pin "2") (pinfunction "2_2") (pintype "bidirectional"))
      (node (ref "D5") (pin "5") (pinfunction "VBUS_5") (pintype "bidirectional"))
      (node (ref "U1") (pin "15") (pinfunction "CELL_VBUS_15") (pintype "bidirectional"))
      (node (ref "USB1") (pin "1") (pinfunction "VBUS_1") (pintype "bidirectional"))
    )
    (net (code "28") (name "CLK1") (class "Default")
      (node (ref "J2") (pin "6") (pinfunction "6_6") (pintype "passive"))
      (node (ref "U1") (pin "98") (pinfunction "RESV_98") (pintype "bidirectional"))
    )
    (net (code "29") (name "G") (class "Default")
      (node (ref "J3") (pin "40") (pinfunction "40_40") (pintype "passive"))
      (node (ref "R13") (pin "2") (pinfunction "2_2") (pintype "passive"))
      (node (ref "TP68") (pin "TP") (pinfunction "PP_TP") (pintype "input"))
      (node (ref "U1") (pin "29") (pinfunction "GREEN_29") (pintype "bidirectional"))
    )
    (net (code "30") (name "GND") (class "Default")
      (node (ref "C1") (pin "2") (pinfunction "2_2") (pintype "passive"))
      (node (ref "C10") (pin "1") (pinfunction "1_1") (pintype "passive"))
      (node (ref "C11") (pin "-") (pinfunction "-_-") (pintype "passive"))
      (node (ref "C12") (pin "2") (pinfunction "2_2") (pintype "bidirectional"))
      (node (ref "C123") (pin "2") (pinfunction "2_2") (pintype "bidirectional"))
      (node (ref "C13") (pin "1") (pinfunction "1_1") (pintype "bidirectional"))
      (node (ref "C14") (pin "1") (pinfunction "1_1") (pintype "bidirectional"))
      (node (ref "C15") (pin "1") (pinfunction "1_1") (pintype "bidirectional"))
      (node (ref "C16") (pin "2") (pinfunction "2_2") (pintype "bidirectional"))
      (node (ref "C17") (pin "2") (pinfunction "2_2") (pintype "bidirectional"))
      (node (ref "C18") (pin "1") (pinfunction "1_1") (pintype "bidirectional"))
      (node (ref "C2") (pin "2") (pinfunction "2_2") (pintype "passive"))
      (node (ref "C20") (pin "1") (pinfunction "1_1") (pintype "bidirectional"))
      (node (ref "C21") (pin "2") (pinfunction "2_2") (pintype "bidirectional"))
      (node (ref "C22") (pin "2") (pinfunction "2_2") (pintype "bidirectional"))
      (node (ref "C23") (pin "2") (pinfunction "2_2") (pintype "passive"))
      (node (ref "C24") (pin "2") (pinfunction "2_2") (pintype "passive"))
      (node (ref "C25") (pin "1") (pinfunction "1_1") (pintype "bidirectional"))
      (node (ref "C26") (pin "2") (pinfunction "2_2") (pintype "bidirectional"))
      (node (ref "C28") (pin "1") (pinfunction "1_1") (pintype "bidirectional"))
      (node (ref "C29") (pin "2") (pinfunction "2_2") (pintype "passive"))
      (node (ref "C3") (pin "1") (pinfunction "1_1") (pintype "passive"))
      (node (ref "C30") (pin "2") (pinfunction "2_2") (pintype "passive"))
      (node (ref "C31") (pin "-") (pinfunction "-_-") (pintype "passive"))
      (node (ref "C32") (pin "2") (pinfunction "2_2") (pintype "passive"))
      (node (ref "C33") (pin "2") (pinfunction "2_2") (pintype "bidirectional"))
      (node (ref "C34") (pin "1") (pinfunction "1_1") (pintype "bidirectional"))
      (node (ref "C35") (pin "1") (pinfunction "1_1") (pintype "bidirectional"))
      (node (ref "C36") (pin "1") (pinfunction "1_1") (pintype "passive"))
      (node (ref "C37") (pin "1") (pinfunction "1_1") (pintype "bidirectional"))
      (node (ref "C38") (pin "1") (pinfunction "1_1") (pintype "passive"))
      (node (ref "C39") (pin "1") (pinfunction "1_1") (pintype "bidirectional"))
      (node (ref "C4") (pin "1") (pinfunction "1_1") (pintype "bidirectional"))
      (node (ref "C5") (pin "2") (pinfunction "2_2") (pintype "bidirectional"))
      (node (ref "C6") (pin "2") (pinfunction "2_2") (pintype "bidirectional"))
      (node (ref "C7") (pin "2") (pinfunction "2_2") (pintype "passive"))
      (node (ref "C8") (pin "1") (pinfunction "1_1") (pintype "bidirectional"))
      (node (ref "C9") (pin "2") (pinfunction "2_2") (pintype "bidirectional"))
      (node (ref "D3") (pin "2") (pinfunction "GND_2") (pintype "bidirectional"))
      (node (ref "D4") (pin "2") (pinfunction "GND_2") (pintype "bidirectional"))
      (node (ref "D5") (pin "2") (pinfunction "GND_2") (pintype "bidirectional"))
      (node (ref "DEBUG") (pin "3") (pinfunction "3_3") (pintype "bidirectional"))
      (node (ref "DEBUG") (pin "5") (pinfunction "5_5") (pintype "bidirectional"))
      (node (ref "DEBUG") (pin "9") (pinfunction "9_9") (pintype "bidirectional"))
      (node (ref "ESD1") (pin "1") (pinfunction "A1_1") (pintype "passive"))
      (node (ref "ESD2") (pin "2") (pinfunction "A2_2") (pintype "passive"))
      (node (ref "J1") (pin "GND@1") (pinfunction "GNDBREAK_GND@1") (pintype "bidirectional"))
      (node (ref "J1") (pin "GND@2") (pinfunction "GND_GND@2") (pintype "bidirectional"))
      (node (ref "J10") (pin "4") (pinfunction "4_4") (pintype "bidirectional"))
      (node (ref "J11") (pin "4") (pinfunction "4_4") (pintype "bidirectional"))
      (node (ref "J15") (pin "1") (pinfunction "1_1") (pintype "passive"))
      (node (ref "J2") (pin "1") (pinfunction "1_1") (pintype "passive"))
      (node (ref "J3") (pin "1") (pinfunction "1_1") (pintype "passive"))
      (node (ref "J3") (pin "11") (pinfunction "11_11") (pintype "passive"))
      (node (ref "J3") (pin "12") (pinfunction "12_12") (pintype "passive"))
      (node (ref "J3") (pin "2") (pinfunction "2_2") (pintype "passive"))
      (node (ref "J3") (pin "31") (pinfunction "31_31") (pintype "passive"))
      (node (ref "J3") (pin "32") (pinfunction "32_32") (pintype "passive"))
      (node (ref "J4") (pin "3") (pinfunction "3_3") (pintype "passive"))
      (node (ref "J7") (pin "29") (pinfunction "29_29") (pintype "passive"))
      (node (ref "J7") (pin "30") (pinfunction "30_30") (pintype "passive"))
      (node (ref "J7") (pin "7") (pinfunction "7_7") (pintype "passive"))
      (node (ref "J7") (pin "8") (pinfunction "8_8") (pintype "passive"))
      (node (ref "J9") (pin "1") (pinfunction "1_1") (pintype "passive"))
      (node (ref "L11_NC") (pin "2") (pinfunction "2_2") (pintype "bidirectional"))
      (node (ref "L12_NC") (pin "2") (pinfunction "2_2") (pintype "bidirectional"))
      (node (ref "L13_NC") (pin "2") (pinfunction "2_2") (pintype "bidirectional"))
      (node (ref "R14") (pin "2") (pinfunction "2_2") (pintype "bidirectional"))
      (node (ref "R26") (pin "2") (pinfunction "2_2") (pintype "bidirectional"))
      (node (ref "R27") (pin "1") (pinfunction "1_1") (pintype "bidirectional"))
      (node (ref "R30") (pin "2") (pinfunction "2_2") (pintype "passive"))
      (node (ref "R32") (pin "2") (pinfunction "2_2") (pintype "bidirectional"))
      (node (ref "R34") (pin "2") (pinfunction "2_2") (pintype "bidirectional"))
      (node (ref "R35") (pin "1") (pinfunction "1_1") (pintype "passive"))
      (node (ref "R36") (pin "2") (pinfunction "2_2") (pintype "passive"))
      (node (ref "R38") (pin "1") (pinfunction "1_1") (pintype "passive"))
      (node (ref "R4") (pin "1") (pinfunction "1_1") (pintype "bidirectional"))
      (node (ref "R40") (pin "1") (pinfunction "1_1") (pintype "passive"))
      (node (ref "R49") (pin "1") (pinfunction "1_1") (pintype "passive"))
      (node (ref "S2") (pin "3") (pinfunction "2_3") (pintype "passive"))
      (node (ref "S3") (pin "3") (pinfunction "2_3") (pintype "passive"))
      (node (ref "S4") (pin "4") (pinfunction "4_4") (pintype "bidirectional"))
      (node (ref "S5") (pin "3") (pinfunction "3_3") (pintype "bidirectional"))
      (node (ref "S6") (pin "1") (pinfunction "1_1") (pintype "bidirectional"))
      (node (ref "S6") (pin "4") (pinfunction "4_4") (pintype "bidirectional"))
      (node (ref "U$10") (pin "P$1") (pinfunction "TP_P$1") (pintype "bidirectional"))
      (node (ref "U1") (pin "1") (pinfunction "GND_1") (pintype "bidirectional"))
      (node (ref "U1") (pin "10") (pinfunction "GND_10") (pintype "bidirectional"))
      (node (ref "U1") (pin "105") (pinfunction "RESV_105") (pintype "bidirectional"))
      (node (ref "U1") (pin "106") (pinfunction "RESV_106") (pintype "bidirectional"))
      (node (ref "U1") (pin "107") (pinfunction "RESV_107") (pintype "bidirectional"))
      (node (ref "U1") (pin "108") (pinfunction "RESV_108") (pintype "bidirectional"))
      (node (ref "U1") (pin "109") (pinfunction "RESV_109") (pintype "bidirectional"))
      (node (ref "U1") (pin "110") (pinfunction "RESV_110") (pintype "bidirectional"))
      (node (ref "U1") (pin "25") (pinfunction "GND_25") (pintype "bidirectional"))
      (node (ref "U1") (pin "31") (pinfunction "GND_31") (pintype "bidirectional"))
      (node (ref "U1") (pin "42") (pinfunction "GND_42") (pintype "bidirectional"))
      (node (ref "U1") (pin "43") (pinfunction "GND_43") (pintype "bidirectional"))
      (node (ref "U1") (pin "48") (pinfunction "GND_48") (pintype "bidirectional"))
      (node (ref "U1") (pin "52") (pinfunction "GND_52") (pintype "bidirectional"))
      (node (ref "U1") (pin "54") (pinfunction "GND_54") (pintype "bidirectional"))
      (node (ref "U1") (pin "63") (pinfunction "AGND/GND_63") (pintype "bidirectional"))
      (node (ref "U1") (pin "67") (pinfunction "GND_67") (pintype "bidirectional"))
      (node (ref "U1") (pin "70") (pinfunction "GND_70") (pintype "bidirectional"))
      (node (ref "U1") (pin "75") (pinfunction "GND_75") (pintype "bidirectional"))
      (node (ref "U1") (pin "8") (pinfunction "GND_8") (pintype "bidirectional"))
      (node (ref "U1") (pin "86") (pinfunction "GND_86") (pintype "bidirectional"))
      (node (ref "U1") (pin "88") (pinfunction "GND_88") (pintype "bidirectional"))
      (node (ref "U1") (pin "89") (pinfunction "GND_89") (pintype "bidirectional"))
      (node (ref "U1") (pin "93") (pinfunction "GND_93") (pintype "bidirectional"))
      (node (ref "U1") (pin "95") (pinfunction "GND_95") (pintype "bidirectional"))
      (node (ref "U2") (pin "3") (pinfunction "GND_3") (pintype "power_in"))
      (node (ref "U3") (pin "-") (pinfunction "-_-") (pintype "passive"))
      (node (ref "U4") (pin "3") (pinfunction "GND_3") (pintype "power_in"))
      (node (ref "U5") (pin "2") (pinfunction "NC_2") (pintype "bidirectional"))
      (node (ref "U5") (pin "3") (pinfunction "NC_3") (pintype "bidirectional"))
      (node (ref "U5") (pin "5") (pinfunction "GND_5") (pintype "bidirectional"))
      (node (ref "U5") (pin "7") (pinfunction "EP_7") (pintype "bidirectional"))
      (node (ref "U6") (pin "1") (pinfunction "GND_1") (pintype "bidirectional"))
      (node (ref "U6") (pin "4") (pinfunction "NC_4") (pintype "bidirectional"))
      (node (ref "U6") (pin "5") (pinfunction "NC_5") (pintype "bidirectional"))
      (node (ref "U8") (pin "3") (pinfunction "GND_3") (pintype "power_in"))
      (node (ref "USB1") (pin "4") (pinfunction "ID_4") (pintype "bidirectional"))
      (node (ref "USB1") (pin "5") (pinfunction "GND3_5") (pintype "bidirectional"))
      (node (ref "USB2") (pin "GND") (pinfunction "GND_GND") (pintype "bidirectional"))
      (node (ref "USB2") (pin "GND2") (pinfunction "GND_GND2") (pintype "bidirectional"))
      (node (ref "USB3") (pin "4") (pinfunction "ID_4") (pintype "bidirectional"))
      (node (ref "USB3") (pin "5") (pinfunction "GND3_5") (pintype "bidirectional"))
      (node (ref "X1") (pin "2") (pinfunction "2_2") (pintype "passive"))
      (node (ref "X1") (pin "3") (pinfunction "2_3") (pintype "passive"))
      (node (ref "X1") (pin "4") (pinfunction "2_4") (pintype "passive"))
      (node (ref "X1") (pin "5") (pinfunction "2_5") (pintype "passive"))
      (node (ref "X2") (pin "2") (pinfunction "2_2") (pintype "passive"))
      (node (ref "X2") (pin "3") (pinfunction "2_3") (pintype "passive"))
      (node (ref "X2") (pin "4") (pinfunction "2_4") (pintype "passive"))
      (node (ref "X2") (pin "5") (pinfunction "2_5") (pintype "passive"))
      (node (ref "X3") (pin "2") (pinfunction "2_2") (pintype "passive"))
      (node (ref "X3") (pin "3") (pinfunction "2_3") (pintype "passive"))
      (node (ref "X3") (pin "4") (pinfunction "2_4") (pintype "passive"))
      (node (ref "X3") (pin "5") (pinfunction "2_5") (pintype "passive"))
    )
    (net (code "31") (name "GNSS_ANT_PWR") (class "Default")
      (node (ref "D1") (pin "1") (pinfunction "P$1_1") (pintype "bidirectional"))
      (node (ref "U1") (pin "91") (pinfunction "GNSS_ANT_PWR_91") (pintype "bidirectional"))
    )
    (net (code "32") (name "GNSS_BAT") (class "Default")
      (node (ref "R37") (pin "2") (pinfunction "2_2") (pintype "passive"))
      (node (ref "U1") (pin "2") (pinfunction "GNSS_BAT_2") (pintype "bidirectional"))
    )
    (net (code "33") (name "GNSS_BOOT") (class "Default")
      (node (ref "U1") (pin "90") (pinfunction "GNSS_BOOT_90") (pintype "bidirectional"))
    )
    (net (code "34") (name "GNSS_LAN_EN") (class "Default")
      (node (ref "U1") (pin "92") (pinfunction "GNSS_LNA_EN_92") (pintype "bidirectional"))
    )
    (net (code "35") (name "GNSS_N") (class "Default")
      (node (ref "R23") (pin "2") (pinfunction "2_2") (pintype "bidirectional"))
      (node (ref "U1") (pin "6") (pinfunction "GNSS_N_6") (pintype "bidirectional"))
    )
    (net (code "36") (name "GNSS_P") (class "Default")
      (node (ref "R24") (pin "2") (pinfunction "2_2") (pintype "bidirectional"))
      (node (ref "U1") (pin "5") (pinfunction "GNSS_P_5") (pintype "bidirectional"))
    )
    (net (code "37") (name "GNSS_RESET") (class "Default")
      (node (ref "U1") (pin "3") (pinfunction "GNSS_RESET_3") (pintype "bidirectional"))
    )
    (net (code "38") (name "GNSS_RF") (class "Default")
      (node (ref "U1") (pin "94") (pinfunction "GNSS_RF_94") (pintype "bidirectional"))
    )
    (net (code "39") (name "GNSS_TIME_PULSE") (class "Default")
      (node (ref "J7") (pin "27") (pinfunction "27_27") (pintype "passive"))
      (node (ref "TP1") (pin "TP") (pinfunction "PP_TP") (pintype "input"))
      (node (ref "U1") (pin "7") (pinfunction "GNSS_PULSE_7") (pintype "bidirectional"))
    )
    (net (code "40") (name "GNSS_VBUS") (class "Default")
      (node (ref "C33") (pin "1") (pinfunction "1_1") (pintype "bidirectional"))
      (node (ref "C35") (pin "2") (pinfunction "2_2") (pintype "bidirectional"))
      (node (ref "U1") (pin "4") (pinfunction "GNSS_VBUS_4") (pintype "bidirectional"))
      (node (ref "U6") (pin "3") (pinfunction "OUT_3") (pintype "bidirectional"))
    )
    (net (code "41") (name "LI+") (class "Default")
      (node (ref "C36") (pin "2") (pinfunction "2_2") (pintype "passive"))
      (node (ref "C37") (pin "2") (pinfunction "2_2") (pintype "bidirectional"))
      (node (ref "J3") (pin "3") (pinfunction "3_3") (pintype "passive"))
      (node (ref "Q1") (pin "3") (pinfunction "3_3") (pintype "bidirectional"))
      (node (ref "TP6") (pin "TP") (pinfunction "PP_TP") (pintype "input"))
      (node (ref "U1") (pin "53") (pinfunction "LI+_53") (pintype "bidirectional"))
    )
    (net (code "42") (name "MCU_N") (class "Default")
      (node (ref "R15") (pin "2") (pinfunction "2_2") (pintype "bidirectional"))
      (node (ref "U1") (pin "68") (pinfunction "MCU_D-_68") (pintype "bidirectional"))
    )
    (net (code "43") (name "MCU_P") (class "Default")
      (node (ref "R16") (pin "2") (pinfunction "2_2") (pintype "bidirectional"))
      (node (ref "U1") (pin "69") (pinfunction "MCU_D+_69") (pintype "bidirectional"))
    )
    (net (code "44") (name "MCU_RX") (class "Default")
      (node (ref "J3") (pin "33") (pinfunction "33_33") (pintype "passive"))
      (node (ref "TP27") (pin "TP") (pinfunction "PP_TP") (pintype "input"))
      (node (ref "U1") (pin "71") (pinfunction "MCU_RX_71") (pintype "bidirectional"))
    )
    (net (code "45") (name "MCU_TX") (class "Default")
      (node (ref "J3") (pin "35") (pinfunction "35_35") (pintype "passive"))
      (node (ref "TP29") (pin "TP") (pinfunction "PP_TP") (pintype "input"))
      (node (ref "U1") (pin "72") (pinfunction "MUC_TX_72") (pintype "bidirectional"))
    )
    (net (code "46") (name "MISO1") (class "Default")
      (node (ref "J2") (pin "4") (pinfunction "4_4") (pintype "passive"))
      (node (ref "U1") (pin "97") (pinfunction "RESV_97") (pintype "bidirectional"))
    )
    (net (code "47") (name "MODE") (class "Default")
      (node (ref "J3") (pin "36") (pinfunction "36_36") (pintype "passive"))
      (node (ref "R9") (pin "2") (pinfunction "2_2") (pintype "bidirectional"))
      (node (ref "S2") (pin "1") (pinfunction "1_1") (pintype "passive"))
      (node (ref "TP66") (pin "TP") (pinfunction "PP_TP") (pintype "input"))
      (node (ref "U1") (pin "32") (pinfunction "MODE_32") (pintype "bidirectional"))
    )
    (net (code "48") (name "MOSI1") (class "Default")
      (node (ref "J2") (pin "2") (pinfunction "2_2") (pintype "passive"))
      (node (ref "U1") (pin "96") (pinfunction "RESV_96") (pintype "bidirectional"))
    )
    (net (code "49") (name "NFC1") (class "Default")
      (node (ref "J7") (pin "4") (pinfunction "4_4") (pintype "passive"))
      (node (ref "NFC1") (pin "2@1") (pinfunction "GND_2@1") (pintype "passive"))
      (node (ref "NFC1") (pin "2@2") (pinfunction "GND_2@2") (pintype "passive"))
      (node (ref "R26") (pin "1") (pinfunction "1_1") (pintype "bidirectional"))
      (node (ref "TP70") (pin "TP") (pinfunction "PP_TP") (pintype "input"))
      (node (ref "U1") (pin "27") (pinfunction "NFC1_27") (pintype "bidirectional"))
    )
    (net (code "50") (name "NFC2") (class "Default")
      (node (ref "J7") (pin "6") (pinfunction "6_6") (pintype "passive"))
      (node (ref "NFC1") (pin "1") (pinfunction "1_1") (pintype "passive"))
      (node (ref "R27") (pin "2") (pinfunction "2_2") (pintype "bidirectional"))
      (node (ref "TP71") (pin "TP") (pinfunction "PP_TP") (pintype "input"))
      (node (ref "U1") (pin "26") (pinfunction "NFC2_26") (pintype "bidirectional"))
    )
    (net (code "51") (name "Net-(C10-Pad2)") (class "Default")
      (node (ref "C10") (pin "2") (pinfunction "2_2") (pintype "passive"))
      (node (ref "R1") (pin "1") (pinfunction "1_1") (pintype "passive"))
      (node (ref "R10") (pin "2") (pinfunction "2_2") (pintype "passive"))
    )
    (net (code "52") (name "Net-(C11-Pad+)") (class "Default")
      (node (ref "C11") (pin "+") (pinfunction "+_+") (pintype "passive"))
      (node (ref "R20") (pin "1") (pinfunction "1_1") (pintype "passive"))
      (node (ref "R37") (pin "1") (pinfunction "1_1") (pintype "passive"))
    )
    (net (code "53") (name "Net-(D1-P$2)") (class "Default")
      (node (ref "D1") (pin "2") (pinfunction "P$2_2") (pintype "bidirectional"))
      (node (ref "R20") (pin "2") (pinfunction "2_2") (pintype "passive"))
    )
    (net (code "54") (name "Net-(D2-P$1)") (class "Default")
      (node (ref "D2") (pin "1") (pinfunction "P$1_1") (pintype "bidirectional"))
      (node (ref "R33") (pin "2") (pinfunction "2_2") (pintype "passive"))
    )
    (net (code "55") (name "Net-(D2-P$2)") (class "Default")
      (node (ref "D2") (pin "2") (pinfunction "P$2_2") (pintype "bidirectional"))
      (node (ref "DEBUG") (pin "1") (pinfunction "1_1") (pintype "bidirectional"))
    )
    (net (code "56") (name "Net-(D3-I{slash}O1)") (class "Default")
      (node (ref "D3") (pin "1") (pinfunction "I/O1_1") (pintype "bidirectional"))
      (node (ref "R16") (pin "1") (pinfunction "1_1") (pintype "bidirectional"))
      (node (ref "USB2") (pin "A6") (pinfunction "D+_A6") (pintype "bidirectional"))
      (node (ref "USB2") (pin "B6") (pinfunction "D+_B6") (pintype "bidirectional"))
    )
    (net (code "57") (name "Net-(D3-I{slash}O2)") (class "Default")
      (node (ref "D3") (pin "3") (pinfunction "I/O2_3") (pintype "bidirectional"))
      (node (ref "R15") (pin "1") (pinfunction "1_1") (pintype "bidirectional"))
      (node (ref "USB2") (pin "A7") (pinfunction "D-_A7") (pintype "bidirectional"))
      (node (ref "USB2") (pin "B7") (pinfunction "D-_B7") (pintype "bidirectional"))
    )
    (net (code "58") (name "Net-(D4-I{slash}O1)") (class "Default")
      (node (ref "D4") (pin "1") (pinfunction "I/O1_1") (pintype "bidirectional"))
      (node (ref "R24") (pin "1") (pinfunction "1_1") (pintype "bidirectional"))
      (node (ref "USB3") (pin "3") (pinfunction "D+_3") (pintype "bidirectional"))
    )
    (net (code "59") (name "Net-(D4-I{slash}O2)") (class "Default")
      (node (ref "D4") (pin "3") (pinfunction "I/O2_3") (pintype "bidirectional"))
      (node (ref "R23") (pin "1") (pinfunction "1_1") (pintype "bidirectional"))
      (node (ref "USB3") (pin "2") (pinfunction "D-_2") (pintype "bidirectional"))
    )
    (net (code "60") (name "Net-(D4-VBUS)") (class "Default")
      (node (ref "C26") (pin "1") (pinfunction "1_1") (pintype "bidirectional"))
      (node (ref "C8") (pin "2") (pinfunction "2_2") (pintype "bidirectional"))
      (node (ref "D4") (pin "5") (pinfunction "VBUS_5") (pintype "bidirectional"))
      (node (ref "R28") (pin "2") (pinfunction "2_2") (pintype "bidirectional"))
      (node (ref "USB3") (pin "1") (pinfunction "VBUS_1") (pintype "bidirectional"))
    )
    (net (code "61") (name "Net-(D5-I{slash}O1)") (class "Default")
      (node (ref "D5") (pin "1") (pinfunction "I/O1_1") (pintype "bidirectional"))
      (node (ref "R25") (pin "1") (pinfunction "1_1") (pintype "bidirectional"))
      (node (ref "USB1") (pin "3") (pinfunction "D+_3") (pintype "bidirectional"))
    )
    (net (code "62") (name "Net-(D5-I{slash}O2)") (class "Default")
      (node (ref "D5") (pin "3") (pinfunction "I/O2_3") (pintype "bidirectional"))
      (node (ref "R21") (pin "1") (pinfunction "1_1") (pintype "bidirectional"))
      (node (ref "USB1") (pin "2") (pinfunction "D-_2") (pintype "bidirectional"))
    )
    (net (code "63") (name "Net-(F1-Pad1)") (class "Default")
      (node (ref "F1") (pin "1") (pinfunction "1_1") (pintype "bidirectional"))
      (node (ref "USB2") (pin "VBUS1") (pinfunction "VBUS_VBUS1") (pintype "bidirectional"))
      (node (ref "USB2") (pin "VBUS2") (pinfunction "VBUS_VBUS2") (pintype "bidirectional"))
    )
    (net (code "64") (name "Net-(F2-Pad2)") (class "Default")
      (node (ref "F2") (pin "2") (pinfunction "2_2") (pintype "bidirectional"))
      (node (ref "J5") (pin "2") (pinfunction "2_2") (pintype "passive"))
    )
    (net (code "65") (name "Net-(J8-Pad2)") (class "Default")
      (node (ref "J8") (pin "2") (pinfunction "2_2") (pintype "passive"))
      (node (ref "LED1") (pin "C") (pinfunction "C_C") (pintype "passive"))
    )
    (net (code "66") (name "Net-(J9-Pad2)") (class "Default")
      (node (ref "J9") (pin "2") (pinfunction "2_2") (pintype "passive"))
      (node (ref "LED2") (pin "C") (pinfunction "C_C") (pintype "passive"))
    )
    (net (code "67") (name "Net-(J12-1)") (class "Default")
      (node (ref "J12") (pin "2") (pinfunction "1_2") (pintype "passive"))
      (node (ref "J14") (pin "1") (pinfunction "1_1") (pintype "passive"))
      (node (ref "J6") (pin "2") (pinfunction "2_2") (pintype "passive"))
    )
    (net (code "68") (name "Net-(J12-2)") (class "Default")
      (node (ref "J12") (pin "1") (pinfunction "2_1") (pintype "passive"))
      (node (ref "J15") (pin "2") (pinfunction "2_2") (pintype "passive"))
      (node (ref "J6") (pin "1") (pinfunction "1_1") (pintype "passive"))
    )
    (net (code "69") (name "Net-(J14-Pad2)") (class "Default")
      (node (ref "J14") (pin "2") (pinfunction "2_2") (pintype "passive"))
      (node (ref "Q2") (pin "3") (pinfunction "3_3") (pintype "bidirectional"))
    )
    (net (code "70") (name "Net-(LED1-PadA)") (class "Default")
      (node (ref "LED1") (pin "A") (pinfunction "A_A") (pintype "passive"))
      (node (ref "R41") (pin "1") (pinfunction "1_1") (pintype "passive"))
    )
    (net (code "71") (name "Net-(LED2-PadA)") (class "Default")
      (node (ref "LED2") (pin "A") (pinfunction "A_A") (pintype "passive"))
      (node (ref "R44") (pin "1") (pinfunction "1_1") (pintype "passive"))
    )
    (net (code "72") (name "Net-(Q1-Pad1)") (class "Default")
      (node (ref "Q1") (pin "1") (pinfunction "1_1") (pintype "bidirectional"))
      (node (ref "Q2") (pin "1") (pinfunction "1_1") (pintype "bidirectional"))
      (node (ref "R29") (pin "1") (pinfunction "1_1") (pintype "bidirectional"))
      (node (ref "S4") (pin "5") (pinfunction "5_5") (pintype "bidirectional"))
    )
    (net (code "73") (name "Net-(Q1-Pad2)") (class "Default")
      (node (ref "Q1") (pin "2") (pinfunction "2_2") (pintype "bidirectional"))
      (node (ref "Q2") (pin "2") (pinfunction "2_2") (pintype "bidirectional"))
      (node (ref "R2") (pin "1") (pinfunction "1_1") (pintype "bidirectional"))
      (node (ref "R29") (pin "2") (pinfunction "2_2") (pintype "bidirectional"))
    )
    (net (code "74") (name "Net-(Q3-G)") (class "Default")
      (node (ref "C27") (pin "1") (pinfunction "1_1") (pintype "bidirectional"))
      (node (ref "Q3") (pin "4") (pinfunction "G_4") (pintype "passive"))
      (node (ref "R19") (pin "1") (pinfunction "1_1") (pintype "bidirectional"))
      (node (ref "R42") (pin "1") (pinfunction "1_1") (pintype "bidirectional"))
      (node (ref "S6") (pin "2") (pinfunction "2_2") (pintype "bidirectional"))
    )
    (net (code "75") (name "Net-(Q4-G)") (class "Default")
      (node (ref "C19") (pin "1") (pinfunction "1_1") (pintype "bidirectional"))
      (node (ref "Q4") (pin "4") (pinfunction "G_4") (pintype "passive"))
      (node (ref "R39") (pin "1") (pinfunction "1_1") (pintype "bidirectional"))
      (node (ref "S6") (pin "5") (pinfunction "5_5") (pintype "bidirectional"))
    )
    (net (code "76") (name "Net-(R2-Pad2)") (class "Default")
      (node (ref "R2") (pin "2") (pinfunction "2_2") (pintype "bidirectional"))
      (node (ref "S4") (pin "6") (pinfunction "6_6") (pintype "bidirectional"))
    )
    (net (code "77") (name "Net-(R5-Pad1)") (class "Default")
      (node (ref "R5") (pin "1") (pinfunction "1_1") (pintype "bidirectional"))
      (node (ref "U3") (pin "+") (pinfunction "+_+") (pintype "passive"))
    )
    (net (code "78") (name "Net-(R5-Pad2)") (class "Default")
      (node (ref "R5") (pin "2") (pinfunction "2_2") (pintype "bidirectional"))
      (node (ref "S5") (pin "1") (pinfunction "1_1") (pintype "bidirectional"))
    )
    (net (code "79") (name "Net-(R18-Pad1)") (class "Default")
      (node (ref "R18") (pin "1") (pinfunction "1_1") (pintype "bidirectional"))
      (node (ref "S6") (pin "6") (pinfunction "6_6") (pintype "bidirectional"))
    )
    (net (code "80") (name "Net-(R19-Pad2)") (class "Default")
      (node (ref "R19") (pin "2") (pinfunction "2_2") (pintype "bidirectional"))
      (node (ref "S6") (pin "3") (pinfunction "3_3") (pintype "bidirectional"))
    )
    (net (code "81") (name "Net-(RGB-2)") (class "Default")
      (node (ref "R87") (pin "1") (pinfunction "1_1") (pintype "passive"))
      (node (ref "RGB") (pin "BLUE") (pinfunction "2_BLUE") (pintype "passive"))
    )
    (net (code "82") (name "Net-(RGB-3)") (class "Default")
      (node (ref "R13") (pin "1") (pinfunction "1_1") (pintype "passive"))
      (node (ref "RGB") (pin "GREEN") (pinfunction "3_GREEN") (pintype "passive"))
    )
    (net (code "83") (name "Net-(RGB-4)") (class "Default")
      (node (ref "R12") (pin "1") (pinfunction "1_1") (pintype "passive"))
      (node (ref "RGB") (pin "RED") (pinfunction "4_RED") (pintype "passive"))
    )
    (net (code "84") (name "Net-(U2-A)") (class "Default")
      (node (ref "R17") (pin "1") (pinfunction "1_1") (pintype "bidirectional"))
      (node (ref "R35") (pin "2") (pinfunction "2_2") (pintype "passive"))
      (node (ref "U2") (pin "2") (pinfunction "A_2") (pintype "bidirectional"))
    )
    (net (code "85") (name "Net-(U4-A)") (class "Default")
      (node (ref "R43") (pin "2") (pinfunction "2_2") (pintype "bidirectional"))
      (node (ref "R47") (pin "1") (pinfunction "1_1") (pintype "passive"))
      (node (ref "U4") (pin "2") (pinfunction "A_2") (pintype "bidirectional"))
    )
    (net (code "86") (name "Net-(U4-Y)") (class "Default")
      (node (ref "R22") (pin "2") (pinfunction "2_2") (pintype "bidirectional"))
      (node (ref "R49") (pin "2") (pinfunction "2_2") (pintype "passive"))
      (node (ref "U4") (pin "4") (pinfunction "Y_4") (pintype "bidirectional"))
    )
    (net (code "87") (name "Net-(U5-EN)") (class "Default")
      (node (ref "R3") (pin "1") (pinfunction "1_1") (pintype "bidirectional"))
      (node (ref "R4") (pin "2") (pinfunction "2_2") (pintype "bidirectional"))
      (node (ref "U5") (pin "4") (pinfunction "EN_4") (pintype "bidirectional"))
    )
    (net (code "88") (name "Net-(U6-IN)") (class "Default")
      (node (ref "C123") (pin "1") (pinfunction "1_1") (pintype "bidirectional"))
      (node (ref "R28") (pin "1") (pinfunction "1_1") (pintype "bidirectional"))
      (node (ref "U6") (pin "2") (pinfunction "IN_2") (pintype "bidirectional"))
    )
    (net (code "89") (name "Net-(U8-A)") (class "Default")
      (node (ref "R31") (pin "1") (pinfunction "1_1") (pintype "passive"))
      (node (ref "U8") (pin "2") (pinfunction "A_2") (pintype "bidirectional"))
    )
    (net (code "90") (name "Net-(USB2-CC1)") (class "Default")
      (node (ref "R36") (pin "1") (pinfunction "1_1") (pintype "passive"))
      (node (ref "USB2") (pin "A5") (pinfunction "CC1_A5") (pintype "bidirectional"))
    )
    (net (code "91") (name "Net-(USB2-CC2)") (class "Default")
      (node (ref "R30") (pin "1") (pinfunction "1_1") (pintype "passive"))
      (node (ref "USB2") (pin "B5") (pinfunction "CC2_B5") (pintype "bidirectional"))
    )
    (net (code "92") (name "PMID") (class "Default")
      (node (ref "C23") (pin "1") (pinfunction "1_1") (pintype "passive"))
      (node (ref "C24") (pin "1") (pinfunction "1_1") (pintype "passive"))
      (node (ref "J3") (pin "4") (pinfunction "4_4") (pintype "passive"))
      (node (ref "U1") (pin "47") (pinfunction "PMID_47") (pintype "bidirectional"))
    )
    (net (code "93") (name "R") (class "Default")
      (node (ref "J3") (pin "38") (pinfunction "38_38") (pintype "passive"))
      (node (ref "R12") (pin "2") (pinfunction "2_2") (pintype "passive"))
      (node (ref "TP67") (pin "TP") (pinfunction "PP_TP") (pintype "input"))
      (node (ref "U1") (pin "30") (pinfunction "RED_30") (pintype "bidirectional"))
    )
    (net (code "94") (name "RESET") (class "Default")
      (node (ref "DEBUG") (pin "10") (pinfunction "10_10") (pintype "bidirectional"))
      (node (ref "J3") (pin "34") (pinfunction "34_34") (pintype "passive"))
      (node (ref "S3") (pin "1") (pinfunction "1_1") (pintype "passive"))
      (node (ref "TP65") (pin "TP") (pinfunction "PP_TP") (pintype "input"))
      (node (ref "U1") (pin "33") (pinfunction "RESET_33") (pintype "bidirectional"))
    )
    (net (code "95") (name "RTC_BAT") (class "Default")
      (node (ref "C20") (pin "2") (pinfunction "2_2") (pintype "bidirectional"))
      (node (ref "J3") (pin "37") (pinfunction "37_37") (pintype "passive"))
      (node (ref "S5") (pin "2") (pinfunction "2_2") (pintype "bidirectional"))
      (node (ref "TP4") (pin "TP") (pinfunction "PP_TP") (pintype "input"))
      (node (ref "U1") (pin "73") (pinfunction "RTC_BAT_73") (pintype "bidirectional"))
    )
    (net (code "96") (name "RTC_BTN") (class "Default")
      (node (ref "J3") (pin "39") (pinfunction "39_39") (pintype "passive"))
      (node (ref "TP37") (pin "TP") (pinfunction "PP_TP") (pintype "input"))
      (node (ref "U1") (pin "74") (pinfunction "RTC_BTN_74") (pintype "bidirectional"))
    )
    (net (code "97") (name "SHIELD") (class "Default")
      (node (ref "C17") (pin "1") (pinfunction "1_1") (pintype "bidirectional"))
      (node (ref "C22") (pin "1") (pinfunction "1_1") (pintype "bidirectional"))
      (node (ref "C9") (pin "1") (pinfunction "1_1") (pintype "bidirectional"))
      (node (ref "L11_NC") (pin "1") (pinfunction "1_1") (pintype "bidirectional"))
      (node (ref "L12_NC") (pin "1") (pinfunction "1_1") (pintype "bidirectional"))
      (node (ref "L13_NC") (pin "1") (pinfunction "1_1") (pintype "bidirectional"))
      (node (ref "R14") (pin "1") (pinfunction "1_1") (pintype "bidirectional"))
      (node (ref "R32") (pin "1") (pinfunction "1_1") (pintype "bidirectional"))
      (node (ref "R34") (pin "1") (pinfunction "1_1") (pintype "bidirectional"))
      (node (ref "USB1") (pin "6") (pinfunction "GND_6") (pintype "bidirectional"))
      (node (ref "USB1") (pin "7") (pinfunction "GND1_7") (pintype "bidirectional"))
      (node (ref "USB1") (pin "8") (pinfunction "GND4_8") (pintype "bidirectional"))
      (node (ref "USB1") (pin "9") (pinfunction "GND5_9") (pintype "bidirectional"))
      (node (ref "USB2") (pin "SHLD1") (pinfunction "SHLD_SHLD1") (pintype "bidirectional"))
      (node (ref "USB2") (pin "SHLD2") (pinfunction "SHLD_SHLD2") (pintype "bidirectional"))
      (node (ref "USB2") (pin "SHLD3") (pinfunction "SHLD_SHLD3") (pintype "bidirectional"))
      (node (ref "USB2") (pin "SHLD4") (pinfunction "SHLD_SHLD4") (pintype "bidirectional"))
      (node (ref "USB2") (pin "SHLD5") (pinfunction "SHLD_SHLD5") (pintype "bidirectional"))
      (node (ref "USB2") (pin "SHLD6") (pinfunction "SHLD_SHLD6") (pintype "bidirectional"))
      (node (ref "USB2") (pin "SHLD7") (pinfunction "SHLD_SHLD7") (pintype "bidirectional"))
      (node (ref "USB2") (pin "SHLD8") (pinfunction "SHLD_SHLD8") (pintype "bidirectional"))
      (node (ref "USB3") (pin "6") (pinfunction "GND_6") (pintype "bidirectional"))
      (node (ref "USB3") (pin "7") (pinfunction "GND1_7") (pintype "bidirectional"))
      (node (ref "USB3") (pin "8") (pinfunction "GND4_8") (pintype "bidirectional"))
      (node (ref "USB3") (pin "9") (pinfunction "GND5_9") (pintype "bidirectional"))
    )
    (net (code "98") (name "SIM_CLK") (class "Default")
      (node (ref "C14") (pin "2") (pinfunction "2_2") (pintype "bidirectional"))
      (node (ref "J2") (pin "5") (pinfunction "5_5") (pintype "passive"))
      (node (ref "U1") (pin "104") (pinfunction "RESV_104") (pintype "bidirectional"))
    )
    (net (code "99") (name "SIM_DATA") (class "Default")
      (node (ref "C15") (pin "2") (pinfunction "2_2") (pintype "bidirectional"))
      (node (ref "J2") (pin "3") (pinfunction "3_3") (pintype "passive"))
      (node (ref "R7") (pin "1") (pinfunction "1_1") (pintype "bidirectional"))
      (node (ref "U1") (pin "103") (pinfunction "RESV_103") (pintype "bidirectional"))
    )
    (net (code "100") (name "SIM_RST") (class "Default")
      (node (ref "C13") (pin "2") (pinfunction "2_2") (pintype "bidirectional"))
      (node (ref "J2") (pin "7") (pinfunction "7_7") (pintype "passive"))
      (node (ref "U1") (pin "102") (pinfunction "RESV_102") (pintype "bidirectional"))
    )
    (net (code "101") (name "SIM_VCC") (class "Default")
      (node (ref "C16") (pin "1") (pinfunction "1_1") (pintype "bidirectional"))
      (node (ref "J2") (pin "9") (pinfunction "9_9") (pintype "passive"))
      (node (ref "R7") (pin "2") (pinfunction "2_2") (pintype "bidirectional"))
      (node (ref "U1") (pin "101") (pinfunction "RESV_101") (pintype "bidirectional"))
    )
    (net (code "102") (name "SOM9") (class "Default")
      (node (ref "J7") (pin "28") (pinfunction "28_28") (pintype "passive"))
      (node (ref "TP28") (pin "TP") (pinfunction "PP_TP") (pintype "input"))
      (node (ref "U1") (pin "9") (pinfunction "NC_9") (pintype "bidirectional"))
    )
    (net (code "103") (name "SOM18") (class "Default")
      (node (ref "J7") (pin "16") (pinfunction "16_16") (pintype "passive"))
      (node (ref "TP75") (pin "TP") (pinfunction "PP_TP") (pintype "input"))
      (node (ref "U1") (pin "18") (pinfunction "NC_18") (pintype "bidirectional"))
    )
    (net (code "104") (name "SOM19") (class "Default")
      (node (ref "J7") (pin "14") (pinfunction "14_14") (pintype "passive"))
      (node (ref "TP74") (pin "TP") (pinfunction "PP_TP") (pintype "input"))
      (node (ref "U1") (pin "19") (pinfunction "NC_19") (pintype "bidirectional"))
    )
    (net (code "105") (name "SOM20") (class "Default")
      (node (ref "J7") (pin "12") (pinfunction "12_12") (pintype "passive"))
      (node (ref "TP73") (pin "TP") (pinfunction "PP_TP") (pintype "input"))
      (node (ref "U1") (pin "20") (pinfunction "NC_20") (pintype "bidirectional"))
    )
    (net (code "106") (name "SOM21") (class "Default")
      (node (ref "J7") (pin "10") (pinfunction "10_10") (pintype "passive"))
      (node (ref "TP31") (pin "TP") (pinfunction "PP_TP") (pintype "input"))
      (node (ref "U1") (pin "21") (pinfunction "NC_21") (pintype "bidirectional"))
    )
    (net (code "107") (name "SOM34") (class "Default")
      (node (ref "J3") (pin "28") (pinfunction "28_28") (pintype "passive"))
      (node (ref "TP3") (pin "TP") (pinfunction "PP_TP") (pintype "input"))
      (node (ref "U1") (pin "34") (pinfunction "NC_34") (pintype "bidirectional"))
    )
    (net (code "108") (name "SOM35") (class "Default")
      (node (ref "J3") (pin "26") (pinfunction "26_26") (pintype "passive"))
      (node (ref "TP2") (pin "TP") (pinfunction "PP_TP") (pintype "input"))
      (node (ref "U1") (pin "35") (pinfunction "NC_35") (pintype "bidirectional"))
    )
    (net (code "109") (name "SOM36") (class "Default")
      (node (ref "J3") (pin "24") (pinfunction "24_24") (pintype "passive"))
      (node (ref "TP64") (pin "TP") (pinfunction "PP_TP") (pintype "input"))
      (node (ref "U1") (pin "36") (pinfunction "NC_36") (pintype "bidirectional"))
    )
    (net (code "110") (name "SOM37") (class "Default")
      (node (ref "J3") (pin "22") (pinfunction "22_22") (pintype "passive"))
      (node (ref "TP63") (pin "TP") (pinfunction "PP_TP") (pintype "input"))
      (node (ref "U1") (pin "37") (pinfunction "NC_37") (pintype "bidirectional"))
    )
    (net (code "111") (name "SOM44") (class "Default")
      (node (ref "J3") (pin "10") (pinfunction "10_10") (pintype "passive"))
      (node (ref "TP33") (pin "TP") (pinfunction "PP_TP") (pintype "input"))
      (node (ref "U1") (pin "44") (pinfunction "NC_44") (pintype "bidirectional"))
    )
    (net (code "112") (name "SOM59") (class "Default")
      (node (ref "J3") (pin "21") (pinfunction "21_21") (pintype "passive"))
      (node (ref "TP20") (pin "TP") (pinfunction "PP_TP") (pintype "input"))
      (node (ref "U1") (pin "59") (pinfunction "NC_59") (pintype "bidirectional"))
    )
    (net (code "113") (name "SOM60") (class "Default")
      (node (ref "J3") (pin "23") (pinfunction "23_23") (pintype "passive"))
      (node (ref "TP26") (pin "TP") (pinfunction "PP_TP") (pintype "input"))
      (node (ref "U1") (pin "60") (pinfunction "NC_60") (pintype "bidirectional"))
    )
    (net (code "114") (name "SOM61") (class "Default")
      (node (ref "J3") (pin "25") (pinfunction "25_25") (pintype "passive"))
      (node (ref "TP13") (pin "TP") (pinfunction "PP_TP") (pintype "input"))
      (node (ref "U1") (pin "61") (pinfunction "NC_61") (pintype "bidirectional"))
    )
    (net (code "115") (name "SOM62") (class "Default")
      (node (ref "J3") (pin "27") (pinfunction "27_27") (pintype "passive"))
      (node (ref "TP14") (pin "TP") (pinfunction "PP_TP") (pintype "input"))
      (node (ref "U1") (pin "62") (pinfunction "NC_62") (pintype "bidirectional"))
    )
    (net (code "116") (name "SOM76") (class "Default")
      (node (ref "J7") (pin "1") (pinfunction "1_1") (pintype "passive"))
      (node (ref "TP46") (pin "TP") (pinfunction "PP_TP") (pintype "input"))
      (node (ref "U1") (pin "76") (pinfunction "NC_76") (pintype "bidirectional"))
    )
    (net (code "117") (name "SOM77") (class "Default")
      (node (ref "J7") (pin "3") (pinfunction "3_3") (pintype "passive"))
      (node (ref "TP51") (pin "TP") (pinfunction "PP_TP") (pintype "input"))
      (node (ref "U1") (pin "77") (pinfunction "NC_77") (pintype "bidirectional"))
    )
    (net (code "118") (name "SOM78") (class "Default")
      (node (ref "J7") (pin "5") (pinfunction "5_5") (pintype "passive"))
      (node (ref "TP52") (pin "TP") (pinfunction "PP_TP") (pintype "input"))
      (node (ref "U1") (pin "78") (pinfunction "NC_78") (pintype "bidirectional"))
    )
    (net (code "119") (name "SOM79") (class "Default")
      (node (ref "J7") (pin "9") (pinfunction "9_9") (pintype "passive"))
      (node (ref "TP16") (pin "TP") (pinfunction "PP_TP") (pintype "input"))
      (node (ref "U1") (pin "79") (pinfunction "NC_79") (pintype "bidirectional"))
    )
    (net (code "120") (name "SOM80") (class "Default")
      (node (ref "J7") (pin "11") (pinfunction "11_11") (pintype "passive"))
      (node (ref "TP53") (pin "TP") (pinfunction "PP_TP") (pintype "input"))
      (node (ref "U1") (pin "80") (pinfunction "NC_80") (pintype "bidirectional"))
    )
    (net (code "121") (name "SOM81") (class "Default")
      (node (ref "J7") (pin "13") (pinfunction "13_13") (pintype "passive"))
      (node (ref "TP54") (pin "TP") (pinfunction "PP_TP") (pintype "input"))
      (node (ref "U1") (pin "81") (pinfunction "NC_81") (pintype "bidirectional"))
    )
    (net (code "122") (name "SOM82") (class "Default")
      (node (ref "J7") (pin "15") (pinfunction "15_15") (pintype "passive"))
      (node (ref "TP55") (pin "TP") (pinfunction "PP_TP") (pintype "input"))
      (node (ref "U1") (pin "82") (pinfunction "NC_82") (pintype "bidirectional"))
    )
    (net (code "123") (name "STAT") (class "Default")
      (node (ref "J3") (pin "7") (pinfunction "7_7") (pintype "passive"))
      (node (ref "J8") (pin "1") (pinfunction "1_1") (pintype "passive"))
      (node (ref "TP8") (pin "TP") (pinfunction "PP_TP") (pintype "input"))
      (node (ref "U1") (pin "50") (pinfunction "STAT_50") (pintype "bidirectional"))
    )
    (net (code "124") (name "SWDCLK") (class "Default")
      (node (ref "DEBUG") (pin "4") (pinfunction "4_4") (pintype "bidirectional"))
      (node (ref "U1") (pin "23") (pinfunction "SWDCLK_23") (pintype "bidirectional"))
    )
    (net (code "125") (name "SWDIO") (class "Default")
      (node (ref "DEBUG") (pin "2") (pinfunction "2_2") (pintype "bidirectional"))
      (node (ref "U1") (pin "22") (pinfunction "SWDIO_22") (pintype "bidirectional"))
    )
    (net (code "126") (name "SWO") (class "Default")
      (node (ref "DEBUG") (pin "6") (pinfunction "6_6") (pintype "bidirectional"))
      (node (ref "U1") (pin "24") (pinfunction "SWO_24") (pintype "bidirectional"))
    )
    (net (code "127") (name "TS") (class "Default")
      (node (ref "J3") (pin "6") (pinfunction "6_6") (pintype "passive"))
      (node (ref "J6") (pin "3") (pinfunction "3_3") (pintype "passive"))
      (node (ref "R38") (pin "2") (pinfunction "2_2") (pintype "passive"))
      (node (ref "TP32") (pin "TP") (pinfunction "PP_TP") (pintype "input"))
      (node (ref "U1") (pin "46") (pinfunction "TS_46") (pintype "bidirectional"))
    )
    (net (code "128") (name "VBUS") (class "Default")
      (node (ref "C19") (pin "2") (pinfunction "2_2") (pintype "bidirectional"))
      (node (ref "C21") (pin "1") (pinfunction "1_1") (pintype "bidirectional"))
      (node (ref "C4") (pin "2") (pinfunction "2_2") (pintype "bidirectional"))
      (node (ref "D3") (pin "5") (pinfunction "VBUS_5") (pintype "bidirectional"))
      (node (ref "F1") (pin "2") (pinfunction "2_2") (pintype "bidirectional"))
      (node (ref "Q4") (pin "1") (pinfunction "S_1") (pintype "passive"))
      (node (ref "Q4") (pin "2") (pinfunction "S_2") (pintype "passive"))
      (node (ref "Q4") (pin "3") (pinfunction "S_3") (pintype "passive"))
      (node (ref "R18") (pin "2") (pinfunction "2_2") (pintype "bidirectional"))
      (node (ref "R39") (pin "2") (pinfunction "2_2") (pintype "bidirectional"))
    )
    (net (code "129") (name "VBUS_SOM") (class "Default")
      (node (ref "C25") (pin "2") (pinfunction "2_2") (pintype "bidirectional"))
      (node (ref "C38") (pin "2") (pinfunction "2_2") (pintype "passive"))
      (node (ref "C39") (pin "2") (pinfunction "2_2") (pintype "bidirectional"))
      (node (ref "J3") (pin "5") (pinfunction "5_5") (pintype "passive"))
      (node (ref "Q4") (pin "5") (pinfunction "D_5") (pintype "passive"))
      (node (ref "Q4") (pin "6") (pinfunction "D_6") (pintype "passive"))
      (node (ref "Q4") (pin "7") (pinfunction "D_7") (pintype "passive"))
      (node (ref "Q4") (pin "8") (pinfunction "D_8") (pintype "passive"))
      (node (ref "TP7") (pin "TP") (pinfunction "PP_TP") (pintype "input"))
      (node (ref "U1") (pin "51") (pinfunction "VBUS_51") (pintype "bidirectional"))
    )
    (net (code "130") (name "VIN") (class "Default")
      (node (ref "C27") (pin "2") (pinfunction "2_2") (pintype "bidirectional"))
      (node (ref "J1") (pin "PWR") (pinfunction "PWR_PWR") (pintype "bidirectional"))
      (node (ref "Q3") (pin "1") (pinfunction "S_1") (pintype "passive"))
      (node (ref "Q3") (pin "2") (pinfunction "S_2") (pintype "passive"))
      (node (ref "Q3") (pin "3") (pinfunction "S_3") (pintype "passive"))
      (node (ref "R42") (pin "2") (pinfunction "2_2") (pintype "bidirectional"))
      (node (ref "U$9") (pin "P$1") (pinfunction "TP_P$1") (pintype "bidirectional"))
    )
    (net (code "131") (name "VIN_SOM") (class "Default")
      (node (ref "C28") (pin "2") (pinfunction "2_2") (pintype "bidirectional"))
      (node (ref "C29") (pin "1") (pinfunction "1_1") (pintype "passive"))
      (node (ref "C30") (pin "1") (pinfunction "1_1") (pintype "passive"))
      (node (ref "C31") (pin "+") (pinfunction "+_+") (pintype "passive"))
      (node (ref "C32") (pin "1") (pinfunction "1_1") (pintype "passive"))
      (node (ref "J3") (pin "9") (pinfunction "9_9") (pintype "passive"))
      (node (ref "Q3") (pin "5") (pinfunction "D_5") (pintype "passive"))
      (node (ref "Q3") (pin "6") (pinfunction "D_6") (pintype "passive"))
      (node (ref "Q3") (pin "7") (pinfunction "D_7") (pintype "passive"))
      (node (ref "Q3") (pin "8") (pinfunction "D_8") (pintype "passive"))
      (node (ref "TP12") (pin "TP") (pinfunction "PP_TP") (pintype "input"))
      (node (ref "U1") (pin "49") (pinfunction "VIN_49") (pintype "bidirectional"))
    )
    (net (code "132") (name "WIFI_BOOT") (class "Default")
      (node (ref "J7") (pin "24") (pinfunction "24_24") (pintype "passive"))
      (node (ref "TP24") (pin "TP") (pinfunction "PP_TP") (pintype "input"))
      (node (ref "U1") (pin "12") (pinfunction "WIFI_BOOT_12") (pintype "bidirectional"))
    )
    (net (code "133") (name "WIFI_EN") (class "Default")
      (node (ref "J7") (pin "26") (pinfunction "26_26") (pintype "passive"))
      (node (ref "TP25") (pin "TP") (pinfunction "PP_TP") (pintype "input"))
      (node (ref "U1") (pin "11") (pinfunction "WIFI_EN_11") (pintype "bidirectional"))
    )
    (net (code "134") (name "WIFI_RXD") (class "Default")
      (node (ref "J7") (pin "20") (pinfunction "20_20") (pintype "passive"))
      (node (ref "TP22") (pin "TP") (pinfunction "PP_TP") (pintype "input"))
      (node (ref "U1") (pin "14") (pinfunction "WIFI_RXD_14") (pintype "bidirectional"))
    )
    (net (code "135") (name "WIFI_TXD") (class "Default")
      (node (ref "J7") (pin "22") (pinfunction "22_22") (pintype "passive"))
      (node (ref "TP23") (pin "TP") (pinfunction "PP_TP") (pintype "input"))
      (node (ref "U1") (pin "13") (pinfunction "WIFI_TXD_13") (pintype "bidirectional"))
    )
    (net (code "136") (name "Y1") (class "Default")
      (node (ref "J2") (pin "10") (pinfunction "10_10") (pintype "passive"))
      (node (ref "U1") (pin "100") (pinfunction "RESV_100") (pintype "bidirectional"))
    )
    (net (code "137") (name "Y5") (class "Default")
      (node (ref "J2") (pin "8") (pinfunction "8_8") (pintype "passive"))
      (node (ref "U1") (pin "99") (pinfunction "RESV_99") (pintype "bidirectional"))
    )
    (net (code "138") (name "unconnected-(D3-I{slash}O3-Pad4)") (class "Default")
      (node (ref "D3") (pin "4") (pinfunction "I/O3_4") (pintype "bidirectional"))
    )
    (net (code "139") (name "unconnected-(D3-I{slash}O4-Pad6)") (class "Default")
      (node (ref "D3") (pin "6") (pinfunction "I/O4_6") (pintype "bidirectional"))
    )
    (net (code "140") (name "unconnected-(D4-I{slash}O3-Pad4)") (class "Default")
      (node (ref "D4") (pin "4") (pinfunction "I/O3_4") (pintype "bidirectional"))
    )
    (net (code "141") (name "unconnected-(D4-I{slash}O4-Pad6)") (class "Default")
      (node (ref "D4") (pin "6") (pinfunction "I/O4_6") (pintype "bidirectional"))
    )
    (net (code "142") (name "unconnected-(D5-I{slash}O3-Pad4)") (class "Default")
      (node (ref "D5") (pin "4") (pinfunction "I/O3_4") (pintype "bidirectional"))
    )
    (net (code "143") (name "unconnected-(D5-I{slash}O4-Pad6)") (class "Default")
      (node (ref "D5") (pin "6") (pinfunction "I/O4_6") (pintype "bidirectional"))
    )
    (net (code "144") (name "unconnected-(DEBUG-Pad7)") (class "Default")
      (node (ref "DEBUG") (pin "7") (pinfunction "7_7") (pintype "bidirectional"))
    )
    (net (code "145") (name "unconnected-(DEBUG-Pad8)") (class "Default")
      (node (ref "DEBUG") (pin "8") (pinfunction "8_8") (pintype "bidirectional"))
    )
    (net (code "146") (name "unconnected-(ESD1-C-Pad3)") (class "Default")
      (node (ref "ESD1") (pin "3") (pinfunction "C_3") (pintype "passive"))
    )
    (net (code "147") (name "unconnected-(ESD2-C-Pad3)") (class "Default")
      (node (ref "ESD2") (pin "3") (pinfunction "C_3") (pintype "passive"))
    )
    (net (code "148") (name "unconnected-(J7-Pad19)") (class "Default")
      (node (ref "J7") (pin "19") (pinfunction "19_19") (pintype "passive"))
    )
    (net (code "149") (name "unconnected-(S4-Pad1)") (class "Default")
      (node (ref "S4") (pin "1") (pinfunction "1_1") (pintype "bidirectional"))
    )
    (net (code "150") (name "unconnected-(S4-Pad2)") (class "Default")
      (node (ref "S4") (pin "2") (pinfunction "2_2") (pintype "bidirectional"))
    )
    (net (code "151") (name "unconnected-(S4-Pad3)") (class "Default")
      (node (ref "S4") (pin "3") (pinfunction "3_3") (pintype "bidirectional"))
    )
    (net (code "152") (name "unconnected-(S5-Pad4)") (class "Default")
      (node (ref "S5") (pin "4") (pinfunction "4_4") (pintype "bidirectional"))
    )
    (net (code "153") (name "unconnected-(S5-Pad5)") (class "Default")
      (node (ref "S5") (pin "5") (pinfunction "5_5") (pintype "bidirectional"))
    )
    (net (code "154") (name "unconnected-(S5-Pad6)") (class "Default")
      (node (ref "S5") (pin "6") (pinfunction "6_6") (pintype "bidirectional"))
    )
    (net (code "155") (name "unconnected-(X1-Pad1)") (class "Default")
      (node (ref "X1") (pin "1") (pinfunction "1_1") (pintype "passive"))
    )
    (net (code "156") (name "unconnected-(X2-Pad1)") (class "Default")
      (node (ref "X2") (pin "1") (pinfunction "1_1") (pintype "passive"))
    )
    (net (code "157") (name "unconnected-(X3-Pad1)") (class "Default")
      (node (ref "X3") (pin "1") (pinfunction "1_1") (pintype "passive"))
    )
  )
)
